# cblockyeeshok.net
KiCad netlist of a schematic drawn in EAGLE
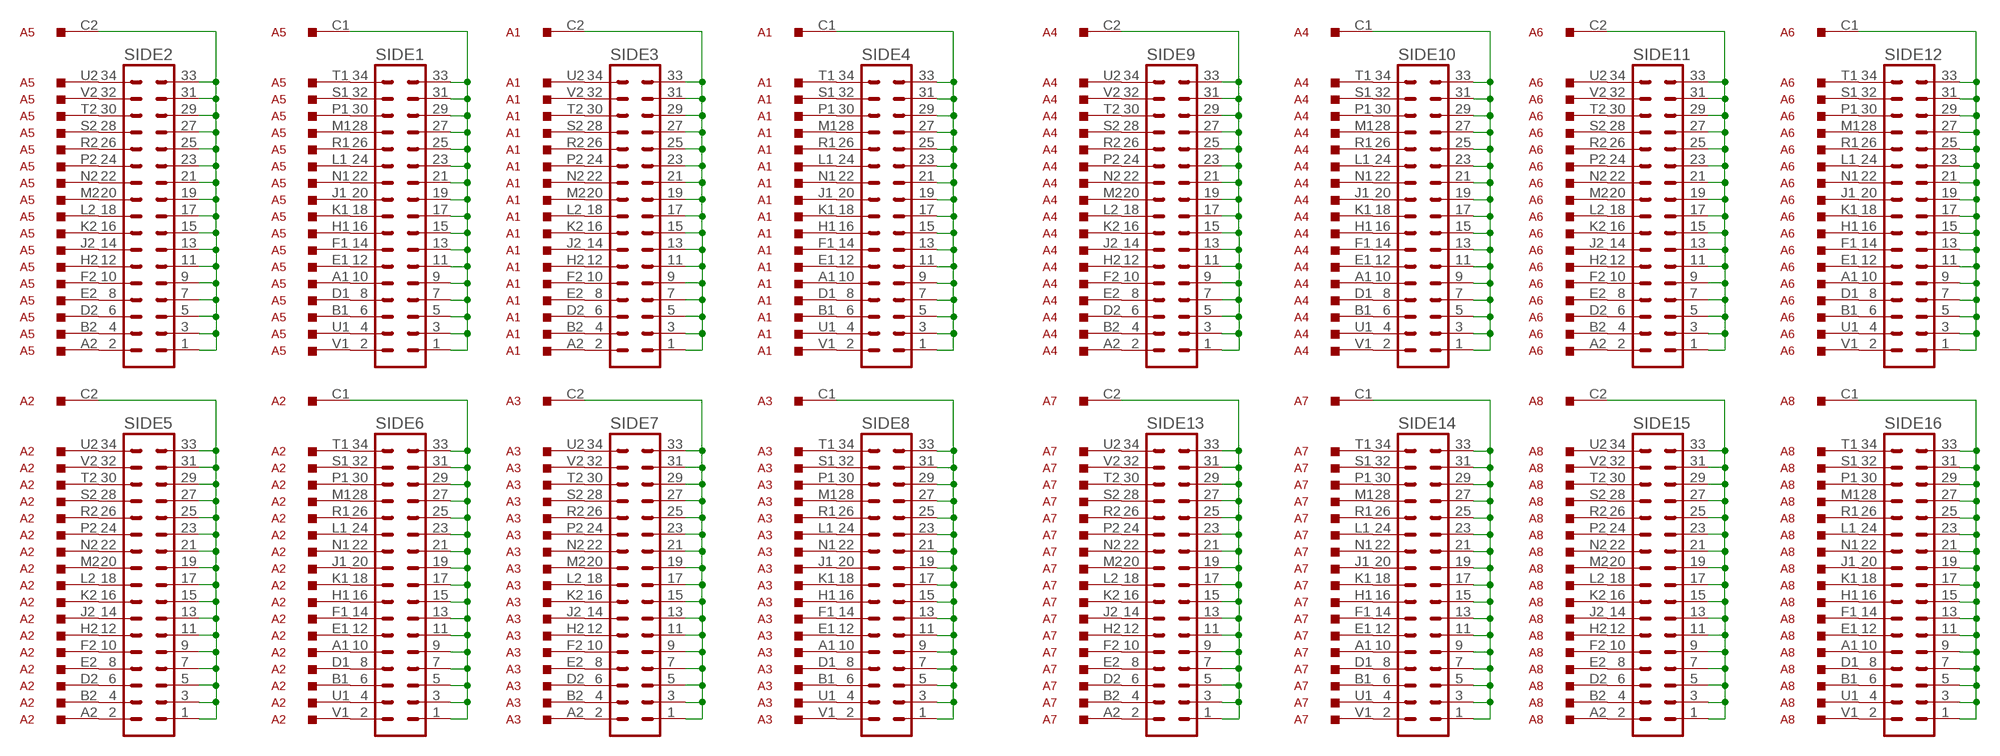
[diagram p0: schematic, sheet 1]

(export (version "E")
  (design (tool "Eeschema 10.0.6"))
  (components
    (comp (ref "A1")
      (value "M916")
      (footprint "eagle-import:H807")
      (libsource (lib "eagle-import") (part "M916"))
    )
    (comp (ref "A2")
      (value "M916")
      (footprint "eagle-import:H807")
      (libsource (lib "eagle-import") (part "M916"))
    )
    (comp (ref "A3")
      (value "M916")
      (footprint "eagle-import:H807")
      (libsource (lib "eagle-import") (part "M916"))
    )
    (comp (ref "A4")
      (value "M916")
      (footprint "eagle-import:H807")
      (libsource (lib "eagle-import") (part "M916"))
    )
    (comp (ref "A5")
      (value "M916")
      (footprint "eagle-import:H807")
      (libsource (lib "eagle-import") (part "M916"))
    )
    (comp (ref "A6")
      (value "M916")
      (footprint "eagle-import:H807")
      (libsource (lib "eagle-import") (part "M916"))
    )
    (comp (ref "A7")
      (value "M916")
      (footprint "eagle-import:H807")
      (libsource (lib "eagle-import") (part "M916"))
    )
    (comp (ref "A8")
      (value "M916")
      (footprint "eagle-import:H807")
      (libsource (lib "eagle-import") (part "M916"))
    )
    (comp (ref "SIDE1")
      (value "MA17-2")
      (footprint "eagle-import:MA17-2")
      (libsource (lib "eagle-import") (part "MA17-2"))
    )
    (comp (ref "SIDE2")
      (value "MA17-2")
      (footprint "eagle-import:MA17-2")
      (libsource (lib "eagle-import") (part "MA17-2"))
    )
    (comp (ref "SIDE3")
      (value "MA17-2")
      (footprint "eagle-import:MA17-2")
      (libsource (lib "eagle-import") (part "MA17-2"))
    )
    (comp (ref "SIDE4")
      (value "MA17-2")
      (footprint "eagle-import:MA17-2")
      (libsource (lib "eagle-import") (part "MA17-2"))
    )
    (comp (ref "SIDE5")
      (value "MA17-2")
      (footprint "eagle-import:MA17-2")
      (libsource (lib "eagle-import") (part "MA17-2"))
    )
    (comp (ref "SIDE6")
      (value "MA17-2")
      (footprint "eagle-import:MA17-2")
      (libsource (lib "eagle-import") (part "MA17-2"))
    )
    (comp (ref "SIDE7")
      (value "MA17-2")
      (footprint "eagle-import:MA17-2")
      (libsource (lib "eagle-import") (part "MA17-2"))
    )
    (comp (ref "SIDE8")
      (value "MA17-2")
      (footprint "eagle-import:MA17-2")
      (libsource (lib "eagle-import") (part "MA17-2"))
    )
    (comp (ref "SIDE9")
      (value "MA17-2")
      (footprint "eagle-import:MA17-2")
      (libsource (lib "eagle-import") (part "MA17-2"))
    )
    (comp (ref "SIDE10")
      (value "MA17-2")
      (footprint "eagle-import:MA17-2")
      (libsource (lib "eagle-import") (part "MA17-2"))
    )
    (comp (ref "SIDE11")
      (value "MA17-2")
      (footprint "eagle-import:MA17-2")
      (libsource (lib "eagle-import") (part "MA17-2"))
    )
    (comp (ref "SIDE12")
      (value "MA17-2")
      (footprint "eagle-import:MA17-2")
      (libsource (lib "eagle-import") (part "MA17-2"))
    )
    (comp (ref "SIDE13")
      (value "MA17-2")
      (footprint "eagle-import:MA17-2")
      (libsource (lib "eagle-import") (part "MA17-2"))
    )
    (comp (ref "SIDE14")
      (value "MA17-2")
      (footprint "eagle-import:MA17-2")
      (libsource (lib "eagle-import") (part "MA17-2"))
    )
    (comp (ref "SIDE15")
      (value "MA17-2")
      (footprint "eagle-import:MA17-2")
      (libsource (lib "eagle-import") (part "MA17-2"))
    )
    (comp (ref "SIDE16")
      (value "MA17-2")
      (footprint "eagle-import:MA17-2")
      (libsource (lib "eagle-import") (part "MA17-2"))
    )
  )
  (nets
    (net (code "1") (name "Net-(A1A-P$2)") (class "Default")
      (node (ref "A1") (pin "A1") (pinfunction "P$2_A1") (pintype "bidirectional"))
      (node (ref "SIDE4") (pin "10") (pinfunction "10_10") (pintype "passive"))
    )
    (net (code "2") (name "Net-(A1AA-P$2)") (class "Default")
      (node (ref "A1") (pin "R1") (pinfunction "P$2_R1") (pintype "bidirectional"))
      (node (ref "SIDE4") (pin "26") (pinfunction "26_26") (pintype "passive"))
    )
    (net (code "3") (name "Net-(A1AB-P$2)") (class "Default")
      (node (ref "A1") (pin "R2") (pinfunction "P$2_R2") (pintype "bidirectional"))
      (node (ref "SIDE3") (pin "26") (pinfunction "26_26") (pintype "passive"))
    )
    (net (code "4") (name "Net-(A1AC-P$2)") (class "Default")
      (node (ref "A1") (pin "S1") (pinfunction "P$2_S1") (pintype "bidirectional"))
      (node (ref "SIDE4") (pin "32") (pinfunction "32_32") (pintype "passive"))
    )
    (net (code "5") (name "Net-(A1AD-P$2)") (class "Default")
      (node (ref "A1") (pin "S2") (pinfunction "P$2_S2") (pintype "bidirectional"))
      (node (ref "SIDE3") (pin "28") (pinfunction "28_28") (pintype "passive"))
    )
    (net (code "6") (name "Net-(A1AE-P$2)") (class "Default")
      (node (ref "A1") (pin "T1") (pinfunction "P$2_T1") (pintype "bidirectional"))
      (node (ref "SIDE4") (pin "34") (pinfunction "34_34") (pintype "passive"))
    )
    (net (code "7") (name "Net-(A1AF-P$2)") (class "Default")
      (node (ref "A1") (pin "T2") (pinfunction "P$2_T2") (pintype "bidirectional"))
      (node (ref "SIDE3") (pin "30") (pinfunction "30_30") (pintype "passive"))
    )
    (net (code "8") (name "Net-(A1AG-P$2)") (class "Default")
      (node (ref "A1") (pin "U1") (pinfunction "P$2_U1") (pintype "bidirectional"))
      (node (ref "SIDE4") (pin "4") (pinfunction "4_4") (pintype "passive"))
    )
    (net (code "9") (name "Net-(A1AH-P$2)") (class "Default")
      (node (ref "A1") (pin "U2") (pinfunction "P$2_U2") (pintype "bidirectional"))
      (node (ref "SIDE3") (pin "34") (pinfunction "34_34") (pintype "passive"))
    )
    (net (code "10") (name "Net-(A1AI-P$2)") (class "Default")
      (node (ref "A1") (pin "V1") (pinfunction "P$2_V1") (pintype "bidirectional"))
      (node (ref "SIDE4") (pin "2") (pinfunction "2_2") (pintype "passive"))
    )
    (net (code "11") (name "Net-(A1AJ-P$2)") (class "Default")
      (node (ref "A1") (pin "V2") (pinfunction "P$2_V2") (pintype "bidirectional"))
      (node (ref "SIDE3") (pin "32") (pinfunction "32_32") (pintype "passive"))
    )
    (net (code "12") (name "Net-(A1B-P$2)") (class "Default")
      (node (ref "A1") (pin "A2") (pinfunction "P$2_A2") (pintype "bidirectional"))
      (node (ref "SIDE3") (pin "2") (pinfunction "2_2") (pintype "passive"))
    )
    (net (code "13") (name "Net-(A1C-P$2)") (class "Default")
      (node (ref "A1") (pin "B1") (pinfunction "P$2_B1") (pintype "bidirectional"))
      (node (ref "SIDE4") (pin "6") (pinfunction "6_6") (pintype "passive"))
    )
    (net (code "14") (name "Net-(A1D-P$2)") (class "Default")
      (node (ref "A1") (pin "B2") (pinfunction "P$2_B2") (pintype "bidirectional"))
      (node (ref "SIDE3") (pin "4") (pinfunction "4_4") (pintype "passive"))
    )
    (net (code "15") (name "Net-(A1E-P$2)") (class "Default")
      (node (ref "A1") (pin "C1") (pinfunction "P$2_C1") (pintype "bidirectional"))
      (node (ref "SIDE4") (pin "1") (pinfunction "1_1") (pintype "passive"))
      (node (ref "SIDE4") (pin "11") (pinfunction "11_11") (pintype "passive"))
      (node (ref "SIDE4") (pin "13") (pinfunction "13_13") (pintype "passive"))
      (node (ref "SIDE4") (pin "15") (pinfunction "15_15") (pintype "passive"))
      (node (ref "SIDE4") (pin "17") (pinfunction "17_17") (pintype "passive"))
      (node (ref "SIDE4") (pin "19") (pinfunction "19_19") (pintype "passive"))
      (node (ref "SIDE4") (pin "21") (pinfunction "21_21") (pintype "passive"))
      (node (ref "SIDE4") (pin "23") (pinfunction "23_23") (pintype "passive"))
      (node (ref "SIDE4") (pin "25") (pinfunction "25_25") (pintype "passive"))
      (node (ref "SIDE4") (pin "27") (pinfunction "27_27") (pintype "passive"))
      (node (ref "SIDE4") (pin "29") (pinfunction "29_29") (pintype "passive"))
      (node (ref "SIDE4") (pin "3") (pinfunction "3_3") (pintype "passive"))
      (node (ref "SIDE4") (pin "31") (pinfunction "31_31") (pintype "passive"))
      (node (ref "SIDE4") (pin "33") (pinfunction "33_33") (pintype "passive"))
      (node (ref "SIDE4") (pin "5") (pinfunction "5_5") (pintype "passive"))
      (node (ref "SIDE4") (pin "7") (pinfunction "7_7") (pintype "passive"))
      (node (ref "SIDE4") (pin "9") (pinfunction "9_9") (pintype "passive"))
    )
    (net (code "16") (name "Net-(A1F-P$2)") (class "Default")
      (node (ref "A1") (pin "C2") (pinfunction "P$2_C2") (pintype "bidirectional"))
      (node (ref "SIDE3") (pin "1") (pinfunction "1_1") (pintype "passive"))
      (node (ref "SIDE3") (pin "11") (pinfunction "11_11") (pintype "passive"))
      (node (ref "SIDE3") (pin "13") (pinfunction "13_13") (pintype "passive"))
      (node (ref "SIDE3") (pin "15") (pinfunction "15_15") (pintype "passive"))
      (node (ref "SIDE3") (pin "17") (pinfunction "17_17") (pintype "passive"))
      (node (ref "SIDE3") (pin "19") (pinfunction "19_19") (pintype "passive"))
      (node (ref "SIDE3") (pin "21") (pinfunction "21_21") (pintype "passive"))
      (node (ref "SIDE3") (pin "23") (pinfunction "23_23") (pintype "passive"))
      (node (ref "SIDE3") (pin "25") (pinfunction "25_25") (pintype "passive"))
      (node (ref "SIDE3") (pin "27") (pinfunction "27_27") (pintype "passive"))
      (node (ref "SIDE3") (pin "29") (pinfunction "29_29") (pintype "passive"))
      (node (ref "SIDE3") (pin "3") (pinfunction "3_3") (pintype "passive"))
      (node (ref "SIDE3") (pin "31") (pinfunction "31_31") (pintype "passive"))
      (node (ref "SIDE3") (pin "33") (pinfunction "33_33") (pintype "passive"))
      (node (ref "SIDE3") (pin "5") (pinfunction "5_5") (pintype "passive"))
      (node (ref "SIDE3") (pin "7") (pinfunction "7_7") (pintype "passive"))
      (node (ref "SIDE3") (pin "9") (pinfunction "9_9") (pintype "passive"))
    )
    (net (code "17") (name "Net-(A1G-P$2)") (class "Default")
      (node (ref "A1") (pin "D1") (pinfunction "P$2_D1") (pintype "bidirectional"))
      (node (ref "SIDE4") (pin "8") (pinfunction "8_8") (pintype "passive"))
    )
    (net (code "18") (name "Net-(A1H-P$2)") (class "Default")
      (node (ref "A1") (pin "D2") (pinfunction "P$2_D2") (pintype "bidirectional"))
      (node (ref "SIDE3") (pin "6") (pinfunction "6_6") (pintype "passive"))
    )
    (net (code "19") (name "Net-(A1I-P$2)") (class "Default")
      (node (ref "A1") (pin "E1") (pinfunction "P$2_E1") (pintype "bidirectional"))
      (node (ref "SIDE4") (pin "12") (pinfunction "12_12") (pintype "passive"))
    )
    (net (code "20") (name "Net-(A1J-P$2)") (class "Default")
      (node (ref "A1") (pin "E2") (pinfunction "P$2_E2") (pintype "bidirectional"))
      (node (ref "SIDE3") (pin "8") (pinfunction "8_8") (pintype "passive"))
    )
    (net (code "21") (name "Net-(A1K-P$2)") (class "Default")
      (node (ref "A1") (pin "F1") (pinfunction "P$2_F1") (pintype "bidirectional"))
      (node (ref "SIDE4") (pin "14") (pinfunction "14_14") (pintype "passive"))
    )
    (net (code "22") (name "Net-(A1L-P$2)") (class "Default")
      (node (ref "A1") (pin "F2") (pinfunction "P$2_F2") (pintype "bidirectional"))
      (node (ref "SIDE3") (pin "10") (pinfunction "10_10") (pintype "passive"))
    )
    (net (code "23") (name "Net-(A1M-P$2)") (class "Default")
      (node (ref "A1") (pin "H1") (pinfunction "P$2_H1") (pintype "bidirectional"))
      (node (ref "SIDE4") (pin "16") (pinfunction "16_16") (pintype "passive"))
    )
    (net (code "24") (name "Net-(A1N-P$2)") (class "Default")
      (node (ref "A1") (pin "H2") (pinfunction "P$2_H2") (pintype "bidirectional"))
      (node (ref "SIDE3") (pin "12") (pinfunction "12_12") (pintype "passive"))
    )
    (net (code "25") (name "Net-(A1O-P$2)") (class "Default")
      (node (ref "A1") (pin "J1") (pinfunction "P$2_J1") (pintype "bidirectional"))
      (node (ref "SIDE4") (pin "20") (pinfunction "20_20") (pintype "passive"))
    )
    (net (code "26") (name "Net-(A1P-P$2)") (class "Default")
      (node (ref "A1") (pin "J2") (pinfunction "P$2_J2") (pintype "bidirectional"))
      (node (ref "SIDE3") (pin "14") (pinfunction "14_14") (pintype "passive"))
    )
    (net (code "27") (name "Net-(A1Q-P$2)") (class "Default")
      (node (ref "A1") (pin "K1") (pinfunction "P$2_K1") (pintype "bidirectional"))
      (node (ref "SIDE4") (pin "18") (pinfunction "18_18") (pintype "passive"))
    )
    (net (code "28") (name "Net-(A1R-P$2)") (class "Default")
      (node (ref "A1") (pin "K2") (pinfunction "P$2_K2") (pintype "bidirectional"))
      (node (ref "SIDE3") (pin "16") (pinfunction "16_16") (pintype "passive"))
    )
    (net (code "29") (name "Net-(A1S-P$2)") (class "Default")
      (node (ref "A1") (pin "L1") (pinfunction "P$2_L1") (pintype "bidirectional"))
      (node (ref "SIDE4") (pin "24") (pinfunction "24_24") (pintype "passive"))
    )
    (net (code "30") (name "Net-(A1T-P$2)") (class "Default")
      (node (ref "A1") (pin "L2") (pinfunction "P$2_L2") (pintype "bidirectional"))
      (node (ref "SIDE3") (pin "18") (pinfunction "18_18") (pintype "passive"))
    )
    (net (code "31") (name "Net-(A1U-P$2)") (class "Default")
      (node (ref "A1") (pin "M1") (pinfunction "P$2_M1") (pintype "bidirectional"))
      (node (ref "SIDE4") (pin "28") (pinfunction "28_28") (pintype "passive"))
    )
    (net (code "32") (name "Net-(A1V-P$2)") (class "Default")
      (node (ref "A1") (pin "M2") (pinfunction "P$2_M2") (pintype "bidirectional"))
      (node (ref "SIDE3") (pin "20") (pinfunction "20_20") (pintype "passive"))
    )
    (net (code "33") (name "Net-(A1W-P$2)") (class "Default")
      (node (ref "A1") (pin "N1") (pinfunction "P$2_N1") (pintype "bidirectional"))
      (node (ref "SIDE4") (pin "22") (pinfunction "22_22") (pintype "passive"))
    )
    (net (code "34") (name "Net-(A1X-P$2)") (class "Default")
      (node (ref "A1") (pin "N2") (pinfunction "P$2_N2") (pintype "bidirectional"))
      (node (ref "SIDE3") (pin "22") (pinfunction "22_22") (pintype "passive"))
    )
    (net (code "35") (name "Net-(A1Y-P$2)") (class "Default")
      (node (ref "A1") (pin "P1") (pinfunction "P$2_P1") (pintype "bidirectional"))
      (node (ref "SIDE4") (pin "30") (pinfunction "30_30") (pintype "passive"))
    )
    (net (code "36") (name "Net-(A1Z-P$2)") (class "Default")
      (node (ref "A1") (pin "P2") (pinfunction "P$2_P2") (pintype "bidirectional"))
      (node (ref "SIDE3") (pin "24") (pinfunction "24_24") (pintype "passive"))
    )
    (net (code "37") (name "Net-(A2A-P$2)") (class "Default")
      (node (ref "A2") (pin "A1") (pinfunction "P$2_A1") (pintype "bidirectional"))
      (node (ref "SIDE6") (pin "10") (pinfunction "10_10") (pintype "passive"))
    )
    (net (code "38") (name "Net-(A2AA-P$2)") (class "Default")
      (node (ref "A2") (pin "R1") (pinfunction "P$2_R1") (pintype "bidirectional"))
      (node (ref "SIDE6") (pin "26") (pinfunction "26_26") (pintype "passive"))
    )
    (net (code "39") (name "Net-(A2AB-P$2)") (class "Default")
      (node (ref "A2") (pin "R2") (pinfunction "P$2_R2") (pintype "bidirectional"))
      (node (ref "SIDE5") (pin "26") (pinfunction "26_26") (pintype "passive"))
    )
    (net (code "40") (name "Net-(A2AC-P$2)") (class "Default")
      (node (ref "A2") (pin "S1") (pinfunction "P$2_S1") (pintype "bidirectional"))
      (node (ref "SIDE6") (pin "32") (pinfunction "32_32") (pintype "passive"))
    )
    (net (code "41") (name "Net-(A2AD-P$2)") (class "Default")
      (node (ref "A2") (pin "S2") (pinfunction "P$2_S2") (pintype "bidirectional"))
      (node (ref "SIDE5") (pin "28") (pinfunction "28_28") (pintype "passive"))
    )
    (net (code "42") (name "Net-(A2AE-P$2)") (class "Default")
      (node (ref "A2") (pin "T1") (pinfunction "P$2_T1") (pintype "bidirectional"))
      (node (ref "SIDE6") (pin "34") (pinfunction "34_34") (pintype "passive"))
    )
    (net (code "43") (name "Net-(A2AF-P$2)") (class "Default")
      (node (ref "A2") (pin "T2") (pinfunction "P$2_T2") (pintype "bidirectional"))
      (node (ref "SIDE5") (pin "30") (pinfunction "30_30") (pintype "passive"))
    )
    (net (code "44") (name "Net-(A2AG-P$2)") (class "Default")
      (node (ref "A2") (pin "U1") (pinfunction "P$2_U1") (pintype "bidirectional"))
      (node (ref "SIDE6") (pin "4") (pinfunction "4_4") (pintype "passive"))
    )
    (net (code "45") (name "Net-(A2AH-P$2)") (class "Default")
      (node (ref "A2") (pin "U2") (pinfunction "P$2_U2") (pintype "bidirectional"))
      (node (ref "SIDE5") (pin "34") (pinfunction "34_34") (pintype "passive"))
    )
    (net (code "46") (name "Net-(A2AI-P$2)") (class "Default")
      (node (ref "A2") (pin "V1") (pinfunction "P$2_V1") (pintype "bidirectional"))
      (node (ref "SIDE6") (pin "2") (pinfunction "2_2") (pintype "passive"))
    )
    (net (code "47") (name "Net-(A2AJ-P$2)") (class "Default")
      (node (ref "A2") (pin "V2") (pinfunction "P$2_V2") (pintype "bidirectional"))
      (node (ref "SIDE5") (pin "32") (pinfunction "32_32") (pintype "passive"))
    )
    (net (code "48") (name "Net-(A2B-P$2)") (class "Default")
      (node (ref "A2") (pin "A2") (pinfunction "P$2_A2") (pintype "bidirectional"))
      (node (ref "SIDE5") (pin "2") (pinfunction "2_2") (pintype "passive"))
    )
    (net (code "49") (name "Net-(A2C-P$2)") (class "Default")
      (node (ref "A2") (pin "B1") (pinfunction "P$2_B1") (pintype "bidirectional"))
      (node (ref "SIDE6") (pin "6") (pinfunction "6_6") (pintype "passive"))
    )
    (net (code "50") (name "Net-(A2D-P$2)") (class "Default")
      (node (ref "A2") (pin "B2") (pinfunction "P$2_B2") (pintype "bidirectional"))
      (node (ref "SIDE5") (pin "4") (pinfunction "4_4") (pintype "passive"))
    )
    (net (code "51") (name "Net-(A2E-P$2)") (class "Default")
      (node (ref "A2") (pin "C1") (pinfunction "P$2_C1") (pintype "bidirectional"))
      (node (ref "SIDE6") (pin "1") (pinfunction "1_1") (pintype "passive"))
      (node (ref "SIDE6") (pin "11") (pinfunction "11_11") (pintype "passive"))
      (node (ref "SIDE6") (pin "13") (pinfunction "13_13") (pintype "passive"))
      (node (ref "SIDE6") (pin "15") (pinfunction "15_15") (pintype "passive"))
      (node (ref "SIDE6") (pin "17") (pinfunction "17_17") (pintype "passive"))
      (node (ref "SIDE6") (pin "19") (pinfunction "19_19") (pintype "passive"))
      (node (ref "SIDE6") (pin "21") (pinfunction "21_21") (pintype "passive"))
      (node (ref "SIDE6") (pin "23") (pinfunction "23_23") (pintype "passive"))
      (node (ref "SIDE6") (pin "25") (pinfunction "25_25") (pintype "passive"))
      (node (ref "SIDE6") (pin "27") (pinfunction "27_27") (pintype "passive"))
      (node (ref "SIDE6") (pin "29") (pinfunction "29_29") (pintype "passive"))
      (node (ref "SIDE6") (pin "3") (pinfunction "3_3") (pintype "passive"))
      (node (ref "SIDE6") (pin "31") (pinfunction "31_31") (pintype "passive"))
      (node (ref "SIDE6") (pin "33") (pinfunction "33_33") (pintype "passive"))
      (node (ref "SIDE6") (pin "5") (pinfunction "5_5") (pintype "passive"))
      (node (ref "SIDE6") (pin "7") (pinfunction "7_7") (pintype "passive"))
      (node (ref "SIDE6") (pin "9") (pinfunction "9_9") (pintype "passive"))
    )
    (net (code "52") (name "Net-(A2F-P$2)") (class "Default")
      (node (ref "A2") (pin "C2") (pinfunction "P$2_C2") (pintype "bidirectional"))
      (node (ref "SIDE5") (pin "1") (pinfunction "1_1") (pintype "passive"))
      (node (ref "SIDE5") (pin "11") (pinfunction "11_11") (pintype "passive"))
      (node (ref "SIDE5") (pin "13") (pinfunction "13_13") (pintype "passive"))
      (node (ref "SIDE5") (pin "15") (pinfunction "15_15") (pintype "passive"))
      (node (ref "SIDE5") (pin "17") (pinfunction "17_17") (pintype "passive"))
      (node (ref "SIDE5") (pin "19") (pinfunction "19_19") (pintype "passive"))
      (node (ref "SIDE5") (pin "21") (pinfunction "21_21") (pintype "passive"))
      (node (ref "SIDE5") (pin "23") (pinfunction "23_23") (pintype "passive"))
      (node (ref "SIDE5") (pin "25") (pinfunction "25_25") (pintype "passive"))
      (node (ref "SIDE5") (pin "27") (pinfunction "27_27") (pintype "passive"))
      (node (ref "SIDE5") (pin "29") (pinfunction "29_29") (pintype "passive"))
      (node (ref "SIDE5") (pin "3") (pinfunction "3_3") (pintype "passive"))
      (node (ref "SIDE5") (pin "31") (pinfunction "31_31") (pintype "passive"))
      (node (ref "SIDE5") (pin "33") (pinfunction "33_33") (pintype "passive"))
      (node (ref "SIDE5") (pin "5") (pinfunction "5_5") (pintype "passive"))
      (node (ref "SIDE5") (pin "7") (pinfunction "7_7") (pintype "passive"))
      (node (ref "SIDE5") (pin "9") (pinfunction "9_9") (pintype "passive"))
    )
    (net (code "53") (name "Net-(A2G-P$2)") (class "Default")
      (node (ref "A2") (pin "D1") (pinfunction "P$2_D1") (pintype "bidirectional"))
      (node (ref "SIDE6") (pin "8") (pinfunction "8_8") (pintype "passive"))
    )
    (net (code "54") (name "Net-(A2H-P$2)") (class "Default")
      (node (ref "A2") (pin "D2") (pinfunction "P$2_D2") (pintype "bidirectional"))
      (node (ref "SIDE5") (pin "6") (pinfunction "6_6") (pintype "passive"))
    )
    (net (code "55") (name "Net-(A2I-P$2)") (class "Default")
      (node (ref "A2") (pin "E1") (pinfunction "P$2_E1") (pintype "bidirectional"))
      (node (ref "SIDE6") (pin "12") (pinfunction "12_12") (pintype "passive"))
    )
    (net (code "56") (name "Net-(A2J-P$2)") (class "Default")
      (node (ref "A2") (pin "E2") (pinfunction "P$2_E2") (pintype "bidirectional"))
      (node (ref "SIDE5") (pin "8") (pinfunction "8_8") (pintype "passive"))
    )
    (net (code "57") (name "Net-(A2K-P$2)") (class "Default")
      (node (ref "A2") (pin "F1") (pinfunction "P$2_F1") (pintype "bidirectional"))
      (node (ref "SIDE6") (pin "14") (pinfunction "14_14") (pintype "passive"))
    )
    (net (code "58") (name "Net-(A2L-P$2)") (class "Default")
      (node (ref "A2") (pin "F2") (pinfunction "P$2_F2") (pintype "bidirectional"))
      (node (ref "SIDE5") (pin "10") (pinfunction "10_10") (pintype "passive"))
    )
    (net (code "59") (name "Net-(A2M-P$2)") (class "Default")
      (node (ref "A2") (pin "H1") (pinfunction "P$2_H1") (pintype "bidirectional"))
      (node (ref "SIDE6") (pin "16") (pinfunction "16_16") (pintype "passive"))
    )
    (net (code "60") (name "Net-(A2N-P$2)") (class "Default")
      (node (ref "A2") (pin "H2") (pinfunction "P$2_H2") (pintype "bidirectional"))
      (node (ref "SIDE5") (pin "12") (pinfunction "12_12") (pintype "passive"))
    )
    (net (code "61") (name "Net-(A2O-P$2)") (class "Default")
      (node (ref "A2") (pin "J1") (pinfunction "P$2_J1") (pintype "bidirectional"))
      (node (ref "SIDE6") (pin "20") (pinfunction "20_20") (pintype "passive"))
    )
    (net (code "62") (name "Net-(A2P-P$2)") (class "Default")
      (node (ref "A2") (pin "J2") (pinfunction "P$2_J2") (pintype "bidirectional"))
      (node (ref "SIDE5") (pin "14") (pinfunction "14_14") (pintype "passive"))
    )
    (net (code "63") (name "Net-(A2Q-P$2)") (class "Default")
      (node (ref "A2") (pin "K1") (pinfunction "P$2_K1") (pintype "bidirectional"))
      (node (ref "SIDE6") (pin "18") (pinfunction "18_18") (pintype "passive"))
    )
    (net (code "64") (name "Net-(A2R-P$2)") (class "Default")
      (node (ref "A2") (pin "K2") (pinfunction "P$2_K2") (pintype "bidirectional"))
      (node (ref "SIDE5") (pin "16") (pinfunction "16_16") (pintype "passive"))
    )
    (net (code "65") (name "Net-(A2S-P$2)") (class "Default")
      (node (ref "A2") (pin "L1") (pinfunction "P$2_L1") (pintype "bidirectional"))
      (node (ref "SIDE6") (pin "24") (pinfunction "24_24") (pintype "passive"))
    )
    (net (code "66") (name "Net-(A2T-P$2)") (class "Default")
      (node (ref "A2") (pin "L2") (pinfunction "P$2_L2") (pintype "bidirectional"))
      (node (ref "SIDE5") (pin "18") (pinfunction "18_18") (pintype "passive"))
    )
    (net (code "67") (name "Net-(A2U-P$2)") (class "Default")
      (node (ref "A2") (pin "M1") (pinfunction "P$2_M1") (pintype "bidirectional"))
      (node (ref "SIDE6") (pin "28") (pinfunction "28_28") (pintype "passive"))
    )
    (net (code "68") (name "Net-(A2V-P$2)") (class "Default")
      (node (ref "A2") (pin "M2") (pinfunction "P$2_M2") (pintype "bidirectional"))
      (node (ref "SIDE5") (pin "20") (pinfunction "20_20") (pintype "passive"))
    )
    (net (code "69") (name "Net-(A2W-P$2)") (class "Default")
      (node (ref "A2") (pin "N1") (pinfunction "P$2_N1") (pintype "bidirectional"))
      (node (ref "SIDE6") (pin "22") (pinfunction "22_22") (pintype "passive"))
    )
    (net (code "70") (name "Net-(A2X-P$2)") (class "Default")
      (node (ref "A2") (pin "N2") (pinfunction "P$2_N2") (pintype "bidirectional"))
      (node (ref "SIDE5") (pin "22") (pinfunction "22_22") (pintype "passive"))
    )
    (net (code "71") (name "Net-(A2Y-P$2)") (class "Default")
      (node (ref "A2") (pin "P1") (pinfunction "P$2_P1") (pintype "bidirectional"))
      (node (ref "SIDE6") (pin "30") (pinfunction "30_30") (pintype "passive"))
    )
    (net (code "72") (name "Net-(A2Z-P$2)") (class "Default")
      (node (ref "A2") (pin "P2") (pinfunction "P$2_P2") (pintype "bidirectional"))
      (node (ref "SIDE5") (pin "24") (pinfunction "24_24") (pintype "passive"))
    )
    (net (code "73") (name "Net-(A3A-P$2)") (class "Default")
      (node (ref "A3") (pin "A1") (pinfunction "P$2_A1") (pintype "bidirectional"))
      (node (ref "SIDE8") (pin "10") (pinfunction "10_10") (pintype "passive"))
    )
    (net (code "74") (name "Net-(A3AA-P$2)") (class "Default")
      (node (ref "A3") (pin "R1") (pinfunction "P$2_R1") (pintype "bidirectional"))
      (node (ref "SIDE8") (pin "26") (pinfunction "26_26") (pintype "passive"))
    )
    (net (code "75") (name "Net-(A3AB-P$2)") (class "Default")
      (node (ref "A3") (pin "R2") (pinfunction "P$2_R2") (pintype "bidirectional"))
      (node (ref "SIDE7") (pin "26") (pinfunction "26_26") (pintype "passive"))
    )
    (net (code "76") (name "Net-(A3AC-P$2)") (class "Default")
      (node (ref "A3") (pin "S1") (pinfunction "P$2_S1") (pintype "bidirectional"))
      (node (ref "SIDE8") (pin "32") (pinfunction "32_32") (pintype "passive"))
    )
    (net (code "77") (name "Net-(A3AD-P$2)") (class "Default")
      (node (ref "A3") (pin "S2") (pinfunction "P$2_S2") (pintype "bidirectional"))
      (node (ref "SIDE7") (pin "28") (pinfunction "28_28") (pintype "passive"))
    )
    (net (code "78") (name "Net-(A3AE-P$2)") (class "Default")
      (node (ref "A3") (pin "T1") (pinfunction "P$2_T1") (pintype "bidirectional"))
      (node (ref "SIDE8") (pin "34") (pinfunction "34_34") (pintype "passive"))
    )
    (net (code "79") (name "Net-(A3AF-P$2)") (class "Default")
      (node (ref "A3") (pin "T2") (pinfunction "P$2_T2") (pintype "bidirectional"))
      (node (ref "SIDE7") (pin "30") (pinfunction "30_30") (pintype "passive"))
    )
    (net (code "80") (name "Net-(A3AG-P$2)") (class "Default")
      (node (ref "A3") (pin "U1") (pinfunction "P$2_U1") (pintype "bidirectional"))
      (node (ref "SIDE8") (pin "4") (pinfunction "4_4") (pintype "passive"))
    )
    (net (code "81") (name "Net-(A3AH-P$2)") (class "Default")
      (node (ref "A3") (pin "U2") (pinfunction "P$2_U2") (pintype "bidirectional"))
      (node (ref "SIDE7") (pin "34") (pinfunction "34_34") (pintype "passive"))
    )
    (net (code "82") (name "Net-(A3AI-P$2)") (class "Default")
      (node (ref "A3") (pin "V1") (pinfunction "P$2_V1") (pintype "bidirectional"))
      (node (ref "SIDE8") (pin "2") (pinfunction "2_2") (pintype "passive"))
    )
    (net (code "83") (name "Net-(A3AJ-P$2)") (class "Default")
      (node (ref "A3") (pin "V2") (pinfunction "P$2_V2") (pintype "bidirectional"))
      (node (ref "SIDE7") (pin "32") (pinfunction "32_32") (pintype "passive"))
    )
    (net (code "84") (name "Net-(A3B-P$2)") (class "Default")
      (node (ref "A3") (pin "A2") (pinfunction "P$2_A2") (pintype "bidirectional"))
      (node (ref "SIDE7") (pin "2") (pinfunction "2_2") (pintype "passive"))
    )
    (net (code "85") (name "Net-(A3C-P$2)") (class "Default")
      (node (ref "A3") (pin "B1") (pinfunction "P$2_B1") (pintype "bidirectional"))
      (node (ref "SIDE8") (pin "6") (pinfunction "6_6") (pintype "passive"))
    )
    (net (code "86") (name "Net-(A3D-P$2)") (class "Default")
      (node (ref "A3") (pin "B2") (pinfunction "P$2_B2") (pintype "bidirectional"))
      (node (ref "SIDE7") (pin "4") (pinfunction "4_4") (pintype "passive"))
    )
    (net (code "87") (name "Net-(A3E-P$2)") (class "Default")
      (node (ref "A3") (pin "C1") (pinfunction "P$2_C1") (pintype "bidirectional"))
      (node (ref "SIDE8") (pin "1") (pinfunction "1_1") (pintype "passive"))
      (node (ref "SIDE8") (pin "11") (pinfunction "11_11") (pintype "passive"))
      (node (ref "SIDE8") (pin "13") (pinfunction "13_13") (pintype "passive"))
      (node (ref "SIDE8") (pin "15") (pinfunction "15_15") (pintype "passive"))
      (node (ref "SIDE8") (pin "17") (pinfunction "17_17") (pintype "passive"))
      (node (ref "SIDE8") (pin "19") (pinfunction "19_19") (pintype "passive"))
      (node (ref "SIDE8") (pin "21") (pinfunction "21_21") (pintype "passive"))
      (node (ref "SIDE8") (pin "23") (pinfunction "23_23") (pintype "passive"))
      (node (ref "SIDE8") (pin "25") (pinfunction "25_25") (pintype "passive"))
      (node (ref "SIDE8") (pin "27") (pinfunction "27_27") (pintype "passive"))
      (node (ref "SIDE8") (pin "29") (pinfunction "29_29") (pintype "passive"))
      (node (ref "SIDE8") (pin "3") (pinfunction "3_3") (pintype "passive"))
      (node (ref "SIDE8") (pin "31") (pinfunction "31_31") (pintype "passive"))
      (node (ref "SIDE8") (pin "33") (pinfunction "33_33") (pintype "passive"))
      (node (ref "SIDE8") (pin "5") (pinfunction "5_5") (pintype "passive"))
      (node (ref "SIDE8") (pin "7") (pinfunction "7_7") (pintype "passive"))
      (node (ref "SIDE8") (pin "9") (pinfunction "9_9") (pintype "passive"))
    )
    (net (code "88") (name "Net-(A3F-P$2)") (class "Default")
      (node (ref "A3") (pin "C2") (pinfunction "P$2_C2") (pintype "bidirectional"))
      (node (ref "SIDE7") (pin "1") (pinfunction "1_1") (pintype "passive"))
      (node (ref "SIDE7") (pin "11") (pinfunction "11_11") (pintype "passive"))
      (node (ref "SIDE7") (pin "13") (pinfunction "13_13") (pintype "passive"))
      (node (ref "SIDE7") (pin "15") (pinfunction "15_15") (pintype "passive"))
      (node (ref "SIDE7") (pin "17") (pinfunction "17_17") (pintype "passive"))
      (node (ref "SIDE7") (pin "19") (pinfunction "19_19") (pintype "passive"))
      (node (ref "SIDE7") (pin "21") (pinfunction "21_21") (pintype "passive"))
      (node (ref "SIDE7") (pin "23") (pinfunction "23_23") (pintype "passive"))
      (node (ref "SIDE7") (pin "25") (pinfunction "25_25") (pintype "passive"))
      (node (ref "SIDE7") (pin "27") (pinfunction "27_27") (pintype "passive"))
      (node (ref "SIDE7") (pin "29") (pinfunction "29_29") (pintype "passive"))
      (node (ref "SIDE7") (pin "3") (pinfunction "3_3") (pintype "passive"))
      (node (ref "SIDE7") (pin "31") (pinfunction "31_31") (pintype "passive"))
      (node (ref "SIDE7") (pin "33") (pinfunction "33_33") (pintype "passive"))
      (node (ref "SIDE7") (pin "5") (pinfunction "5_5") (pintype "passive"))
      (node (ref "SIDE7") (pin "7") (pinfunction "7_7") (pintype "passive"))
      (node (ref "SIDE7") (pin "9") (pinfunction "9_9") (pintype "passive"))
    )
    (net (code "89") (name "Net-(A3G-P$2)") (class "Default")
      (node (ref "A3") (pin "D1") (pinfunction "P$2_D1") (pintype "bidirectional"))
      (node (ref "SIDE8") (pin "8") (pinfunction "8_8") (pintype "passive"))
    )
    (net (code "90") (name "Net-(A3H-P$2)") (class "Default")
      (node (ref "A3") (pin "D2") (pinfunction "P$2_D2") (pintype "bidirectional"))
      (node (ref "SIDE7") (pin "6") (pinfunction "6_6") (pintype "passive"))
    )
    (net (code "91") (name "Net-(A3I-P$2)") (class "Default")
      (node (ref "A3") (pin "E1") (pinfunction "P$2_E1") (pintype "bidirectional"))
      (node (ref "SIDE8") (pin "12") (pinfunction "12_12") (pintype "passive"))
    )
    (net (code "92") (name "Net-(A3J-P$2)") (class "Default")
      (node (ref "A3") (pin "E2") (pinfunction "P$2_E2") (pintype "bidirectional"))
      (node (ref "SIDE7") (pin "8") (pinfunction "8_8") (pintype "passive"))
    )
    (net (code "93") (name "Net-(A3K-P$2)") (class "Default")
      (node (ref "A3") (pin "F1") (pinfunction "P$2_F1") (pintype "bidirectional"))
      (node (ref "SIDE8") (pin "14") (pinfunction "14_14") (pintype "passive"))
    )
    (net (code "94") (name "Net-(A3L-P$2)") (class "Default")
      (node (ref "A3") (pin "F2") (pinfunction "P$2_F2") (pintype "bidirectional"))
      (node (ref "SIDE7") (pin "10") (pinfunction "10_10") (pintype "passive"))
    )
    (net (code "95") (name "Net-(A3M-P$2)") (class "Default")
      (node (ref "A3") (pin "H1") (pinfunction "P$2_H1") (pintype "bidirectional"))
      (node (ref "SIDE8") (pin "16") (pinfunction "16_16") (pintype "passive"))
    )
    (net (code "96") (name "Net-(A3N-P$2)") (class "Default")
      (node (ref "A3") (pin "H2") (pinfunction "P$2_H2") (pintype "bidirectional"))
      (node (ref "SIDE7") (pin "12") (pinfunction "12_12") (pintype "passive"))
    )
    (net (code "97") (name "Net-(A3O-P$2)") (class "Default")
      (node (ref "A3") (pin "J1") (pinfunction "P$2_J1") (pintype "bidirectional"))
      (node (ref "SIDE8") (pin "20") (pinfunction "20_20") (pintype "passive"))
    )
    (net (code "98") (name "Net-(A3P-P$2)") (class "Default")
      (node (ref "A3") (pin "J2") (pinfunction "P$2_J2") (pintype "bidirectional"))
      (node (ref "SIDE7") (pin "14") (pinfunction "14_14") (pintype "passive"))
    )
    (net (code "99") (name "Net-(A3Q-P$2)") (class "Default")
      (node (ref "A3") (pin "K1") (pinfunction "P$2_K1") (pintype "bidirectional"))
      (node (ref "SIDE8") (pin "18") (pinfunction "18_18") (pintype "passive"))
    )
    (net (code "100") (name "Net-(A3R-P$2)") (class "Default")
      (node (ref "A3") (pin "K2") (pinfunction "P$2_K2") (pintype "bidirectional"))
      (node (ref "SIDE7") (pin "16") (pinfunction "16_16") (pintype "passive"))
    )
    (net (code "101") (name "Net-(A3S-P$2)") (class "Default")
      (node (ref "A3") (pin "L1") (pinfunction "P$2_L1") (pintype "bidirectional"))
      (node (ref "SIDE8") (pin "24") (pinfunction "24_24") (pintype "passive"))
    )
    (net (code "102") (name "Net-(A3T-P$2)") (class "Default")
      (node (ref "A3") (pin "L2") (pinfunction "P$2_L2") (pintype "bidirectional"))
      (node (ref "SIDE7") (pin "18") (pinfunction "18_18") (pintype "passive"))
    )
    (net (code "103") (name "Net-(A3U-P$2)") (class "Default")
      (node (ref "A3") (pin "M1") (pinfunction "P$2_M1") (pintype "bidirectional"))
      (node (ref "SIDE8") (pin "28") (pinfunction "28_28") (pintype "passive"))
    )
    (net (code "104") (name "Net-(A3V-P$2)") (class "Default")
      (node (ref "A3") (pin "M2") (pinfunction "P$2_M2") (pintype "bidirectional"))
      (node (ref "SIDE7") (pin "20") (pinfunction "20_20") (pintype "passive"))
    )
    (net (code "105") (name "Net-(A3W-P$2)") (class "Default")
      (node (ref "A3") (pin "N1") (pinfunction "P$2_N1") (pintype "bidirectional"))
      (node (ref "SIDE8") (pin "22") (pinfunction "22_22") (pintype "passive"))
    )
    (net (code "106") (name "Net-(A3X-P$2)") (class "Default")
      (node (ref "A3") (pin "N2") (pinfunction "P$2_N2") (pintype "bidirectional"))
      (node (ref "SIDE7") (pin "22") (pinfunction "22_22") (pintype "passive"))
    )
    (net (code "107") (name "Net-(A3Y-P$2)") (class "Default")
      (node (ref "A3") (pin "P1") (pinfunction "P$2_P1") (pintype "bidirectional"))
      (node (ref "SIDE8") (pin "30") (pinfunction "30_30") (pintype "passive"))
    )
    (net (code "108") (name "Net-(A3Z-P$2)") (class "Default")
      (node (ref "A3") (pin "P2") (pinfunction "P$2_P2") (pintype "bidirectional"))
      (node (ref "SIDE7") (pin "24") (pinfunction "24_24") (pintype "passive"))
    )
    (net (code "109") (name "Net-(A4A-P$2)") (class "Default")
      (node (ref "A4") (pin "A1") (pinfunction "P$2_A1") (pintype "bidirectional"))
      (node (ref "SIDE10") (pin "10") (pinfunction "10_10") (pintype "passive"))
    )
    (net (code "110") (name "Net-(A4AA-P$2)") (class "Default")
      (node (ref "A4") (pin "R1") (pinfunction "P$2_R1") (pintype "bidirectional"))
      (node (ref "SIDE10") (pin "26") (pinfunction "26_26") (pintype "passive"))
    )
    (net (code "111") (name "Net-(A4AB-P$2)") (class "Default")
      (node (ref "A4") (pin "R2") (pinfunction "P$2_R2") (pintype "bidirectional"))
      (node (ref "SIDE9") (pin "26") (pinfunction "26_26") (pintype "passive"))
    )
    (net (code "112") (name "Net-(A4AC-P$2)") (class "Default")
      (node (ref "A4") (pin "S1") (pinfunction "P$2_S1") (pintype "bidirectional"))
      (node (ref "SIDE10") (pin "32") (pinfunction "32_32") (pintype "passive"))
    )
    (net (code "113") (name "Net-(A4AD-P$2)") (class "Default")
      (node (ref "A4") (pin "S2") (pinfunction "P$2_S2") (pintype "bidirectional"))
      (node (ref "SIDE9") (pin "28") (pinfunction "28_28") (pintype "passive"))
    )
    (net (code "114") (name "Net-(A4AE-P$2)") (class "Default")
      (node (ref "A4") (pin "T1") (pinfunction "P$2_T1") (pintype "bidirectional"))
      (node (ref "SIDE10") (pin "34") (pinfunction "34_34") (pintype "passive"))
    )
    (net (code "115") (name "Net-(A4AF-P$2)") (class "Default")
      (node (ref "A4") (pin "T2") (pinfunction "P$2_T2") (pintype "bidirectional"))
      (node (ref "SIDE9") (pin "30") (pinfunction "30_30") (pintype "passive"))
    )
    (net (code "116") (name "Net-(A4AG-P$2)") (class "Default")
      (node (ref "A4") (pin "U1") (pinfunction "P$2_U1") (pintype "bidirectional"))
      (node (ref "SIDE10") (pin "4") (pinfunction "4_4") (pintype "passive"))
    )
    (net (code "117") (name "Net-(A4AH-P$2)") (class "Default")
      (node (ref "A4") (pin "U2") (pinfunction "P$2_U2") (pintype "bidirectional"))
      (node (ref "SIDE9") (pin "34") (pinfunction "34_34") (pintype "passive"))
    )
    (net (code "118") (name "Net-(A4AI-P$2)") (class "Default")
      (node (ref "A4") (pin "V1") (pinfunction "P$2_V1") (pintype "bidirectional"))
      (node (ref "SIDE10") (pin "2") (pinfunction "2_2") (pintype "passive"))
    )
    (net (code "119") (name "Net-(A4AJ-P$2)") (class "Default")
      (node (ref "A4") (pin "V2") (pinfunction "P$2_V2") (pintype "bidirectional"))
      (node (ref "SIDE9") (pin "32") (pinfunction "32_32") (pintype "passive"))
    )
    (net (code "120") (name "Net-(A4B-P$2)") (class "Default")
      (node (ref "A4") (pin "A2") (pinfunction "P$2_A2") (pintype "bidirectional"))
      (node (ref "SIDE9") (pin "2") (pinfunction "2_2") (pintype "passive"))
    )
    (net (code "121") (name "Net-(A4C-P$2)") (class "Default")
      (node (ref "A4") (pin "B1") (pinfunction "P$2_B1") (pintype "bidirectional"))
      (node (ref "SIDE10") (pin "6") (pinfunction "6_6") (pintype "passive"))
    )
    (net (code "122") (name "Net-(A4D-P$2)") (class "Default")
      (node (ref "A4") (pin "B2") (pinfunction "P$2_B2") (pintype "bidirectional"))
      (node (ref "SIDE9") (pin "4") (pinfunction "4_4") (pintype "passive"))
    )
    (net (code "123") (name "Net-(A4E-P$2)") (class "Default")
      (node (ref "A4") (pin "C1") (pinfunction "P$2_C1") (pintype "bidirectional"))
      (node (ref "SIDE10") (pin "1") (pinfunction "1_1") (pintype "passive"))
      (node (ref "SIDE10") (pin "11") (pinfunction "11_11") (pintype "passive"))
      (node (ref "SIDE10") (pin "13") (pinfunction "13_13") (pintype "passive"))
      (node (ref "SIDE10") (pin "15") (pinfunction "15_15") (pintype "passive"))
      (node (ref "SIDE10") (pin "17") (pinfunction "17_17") (pintype "passive"))
      (node (ref "SIDE10") (pin "19") (pinfunction "19_19") (pintype "passive"))
      (node (ref "SIDE10") (pin "21") (pinfunction "21_21") (pintype "passive"))
      (node (ref "SIDE10") (pin "23") (pinfunction "23_23") (pintype "passive"))
      (node (ref "SIDE10") (pin "25") (pinfunction "25_25") (pintype "passive"))
      (node (ref "SIDE10") (pin "27") (pinfunction "27_27") (pintype "passive"))
      (node (ref "SIDE10") (pin "29") (pinfunction "29_29") (pintype "passive"))
      (node (ref "SIDE10") (pin "3") (pinfunction "3_3") (pintype "passive"))
      (node (ref "SIDE10") (pin "31") (pinfunction "31_31") (pintype "passive"))
      (node (ref "SIDE10") (pin "33") (pinfunction "33_33") (pintype "passive"))
      (node (ref "SIDE10") (pin "5") (pinfunction "5_5") (pintype "passive"))
      (node (ref "SIDE10") (pin "7") (pinfunction "7_7") (pintype "passive"))
      (node (ref "SIDE10") (pin "9") (pinfunction "9_9") (pintype "passive"))
    )
    (net (code "124") (name "Net-(A4F-P$2)") (class "Default")
      (node (ref "A4") (pin "C2") (pinfunction "P$2_C2") (pintype "bidirectional"))
      (node (ref "SIDE9") (pin "1") (pinfunction "1_1") (pintype "passive"))
      (node (ref "SIDE9") (pin "11") (pinfunction "11_11") (pintype "passive"))
      (node (ref "SIDE9") (pin "13") (pinfunction "13_13") (pintype "passive"))
      (node (ref "SIDE9") (pin "15") (pinfunction "15_15") (pintype "passive"))
      (node (ref "SIDE9") (pin "17") (pinfunction "17_17") (pintype "passive"))
      (node (ref "SIDE9") (pin "19") (pinfunction "19_19") (pintype "passive"))
      (node (ref "SIDE9") (pin "21") (pinfunction "21_21") (pintype "passive"))
      (node (ref "SIDE9") (pin "23") (pinfunction "23_23") (pintype "passive"))
      (node (ref "SIDE9") (pin "25") (pinfunction "25_25") (pintype "passive"))
      (node (ref "SIDE9") (pin "27") (pinfunction "27_27") (pintype "passive"))
      (node (ref "SIDE9") (pin "29") (pinfunction "29_29") (pintype "passive"))
      (node (ref "SIDE9") (pin "3") (pinfunction "3_3") (pintype "passive"))
      (node (ref "SIDE9") (pin "31") (pinfunction "31_31") (pintype "passive"))
      (node (ref "SIDE9") (pin "33") (pinfunction "33_33") (pintype "passive"))
      (node (ref "SIDE9") (pin "5") (pinfunction "5_5") (pintype "passive"))
      (node (ref "SIDE9") (pin "7") (pinfunction "7_7") (pintype "passive"))
      (node (ref "SIDE9") (pin "9") (pinfunction "9_9") (pintype "passive"))
    )
    (net (code "125") (name "Net-(A4G-P$2)") (class "Default")
      (node (ref "A4") (pin "D1") (pinfunction "P$2_D1") (pintype "bidirectional"))
      (node (ref "SIDE10") (pin "8") (pinfunction "8_8") (pintype "passive"))
    )
    (net (code "126") (name "Net-(A4H-P$2)") (class "Default")
      (node (ref "A4") (pin "D2") (pinfunction "P$2_D2") (pintype "bidirectional"))
      (node (ref "SIDE9") (pin "6") (pinfunction "6_6") (pintype "passive"))
    )
    (net (code "127") (name "Net-(A4I-P$2)") (class "Default")
      (node (ref "A4") (pin "E1") (pinfunction "P$2_E1") (pintype "bidirectional"))
      (node (ref "SIDE10") (pin "12") (pinfunction "12_12") (pintype "passive"))
    )
    (net (code "128") (name "Net-(A4J-P$2)") (class "Default")
      (node (ref "A4") (pin "E2") (pinfunction "P$2_E2") (pintype "bidirectional"))
      (node (ref "SIDE9") (pin "8") (pinfunction "8_8") (pintype "passive"))
    )
    (net (code "129") (name "Net-(A4K-P$2)") (class "Default")
      (node (ref "A4") (pin "F1") (pinfunction "P$2_F1") (pintype "bidirectional"))
      (node (ref "SIDE10") (pin "14") (pinfunction "14_14") (pintype "passive"))
    )
    (net (code "130") (name "Net-(A4L-P$2)") (class "Default")
      (node (ref "A4") (pin "F2") (pinfunction "P$2_F2") (pintype "bidirectional"))
      (node (ref "SIDE9") (pin "10") (pinfunction "10_10") (pintype "passive"))
    )
    (net (code "131") (name "Net-(A4M-P$2)") (class "Default")
      (node (ref "A4") (pin "H1") (pinfunction "P$2_H1") (pintype "bidirectional"))
      (node (ref "SIDE10") (pin "16") (pinfunction "16_16") (pintype "passive"))
    )
    (net (code "132") (name "Net-(A4N-P$2)") (class "Default")
      (node (ref "A4") (pin "H2") (pinfunction "P$2_H2") (pintype "bidirectional"))
      (node (ref "SIDE9") (pin "12") (pinfunction "12_12") (pintype "passive"))
    )
    (net (code "133") (name "Net-(A4O-P$2)") (class "Default")
      (node (ref "A4") (pin "J1") (pinfunction "P$2_J1") (pintype "bidirectional"))
      (node (ref "SIDE10") (pin "20") (pinfunction "20_20") (pintype "passive"))
    )
    (net (code "134") (name "Net-(A4P-P$2)") (class "Default")
      (node (ref "A4") (pin "J2") (pinfunction "P$2_J2") (pintype "bidirectional"))
      (node (ref "SIDE9") (pin "14") (pinfunction "14_14") (pintype "passive"))
    )
    (net (code "135") (name "Net-(A4Q-P$2)") (class "Default")
      (node (ref "A4") (pin "K1") (pinfunction "P$2_K1") (pintype "bidirectional"))
      (node (ref "SIDE10") (pin "18") (pinfunction "18_18") (pintype "passive"))
    )
    (net (code "136") (name "Net-(A4R-P$2)") (class "Default")
      (node (ref "A4") (pin "K2") (pinfunction "P$2_K2") (pintype "bidirectional"))
      (node (ref "SIDE9") (pin "16") (pinfunction "16_16") (pintype "passive"))
    )
    (net (code "137") (name "Net-(A4S-P$2)") (class "Default")
      (node (ref "A4") (pin "L1") (pinfunction "P$2_L1") (pintype "bidirectional"))
      (node (ref "SIDE10") (pin "24") (pinfunction "24_24") (pintype "passive"))
    )
    (net (code "138") (name "Net-(A4T-P$2)") (class "Default")
      (node (ref "A4") (pin "L2") (pinfunction "P$2_L2") (pintype "bidirectional"))
      (node (ref "SIDE9") (pin "18") (pinfunction "18_18") (pintype "passive"))
    )
    (net (code "139") (name "Net-(A4U-P$2)") (class "Default")
      (node (ref "A4") (pin "M1") (pinfunction "P$2_M1") (pintype "bidirectional"))
      (node (ref "SIDE10") (pin "28") (pinfunction "28_28") (pintype "passive"))
    )
    (net (code "140") (name "Net-(A4V-P$2)") (class "Default")
      (node (ref "A4") (pin "M2") (pinfunction "P$2_M2") (pintype "bidirectional"))
      (node (ref "SIDE9") (pin "20") (pinfunction "20_20") (pintype "passive"))
    )
    (net (code "141") (name "Net-(A4W-P$2)") (class "Default")
      (node (ref "A4") (pin "N1") (pinfunction "P$2_N1") (pintype "bidirectional"))
      (node (ref "SIDE10") (pin "22") (pinfunction "22_22") (pintype "passive"))
    )
    (net (code "142") (name "Net-(A4X-P$2)") (class "Default")
      (node (ref "A4") (pin "N2") (pinfunction "P$2_N2") (pintype "bidirectional"))
      (node (ref "SIDE9") (pin "22") (pinfunction "22_22") (pintype "passive"))
    )
    (net (code "143") (name "Net-(A4Y-P$2)") (class "Default")
      (node (ref "A4") (pin "P1") (pinfunction "P$2_P1") (pintype "bidirectional"))
      (node (ref "SIDE10") (pin "30") (pinfunction "30_30") (pintype "passive"))
    )
    (net (code "144") (name "Net-(A4Z-P$2)") (class "Default")
      (node (ref "A4") (pin "P2") (pinfunction "P$2_P2") (pintype "bidirectional"))
      (node (ref "SIDE9") (pin "24") (pinfunction "24_24") (pintype "passive"))
    )
    (net (code "145") (name "Net-(A5A-P$2)") (class "Default")
      (node (ref "A5") (pin "A1") (pinfunction "P$2_A1") (pintype "bidirectional"))
      (node (ref "SIDE1") (pin "10") (pinfunction "10_10") (pintype "passive"))
    )
    (net (code "146") (name "Net-(A5AA-P$2)") (class "Default")
      (node (ref "A5") (pin "R1") (pinfunction "P$2_R1") (pintype "bidirectional"))
      (node (ref "SIDE1") (pin "26") (pinfunction "26_26") (pintype "passive"))
    )
    (net (code "147") (name "Net-(A5AB-P$2)") (class "Default")
      (node (ref "A5") (pin "R2") (pinfunction "P$2_R2") (pintype "bidirectional"))
      (node (ref "SIDE2") (pin "26") (pinfunction "26_26") (pintype "passive"))
    )
    (net (code "148") (name "Net-(A5AC-P$2)") (class "Default")
      (node (ref "A5") (pin "S1") (pinfunction "P$2_S1") (pintype "bidirectional"))
      (node (ref "SIDE1") (pin "32") (pinfunction "32_32") (pintype "passive"))
    )
    (net (code "149") (name "Net-(A5AD-P$2)") (class "Default")
      (node (ref "A5") (pin "S2") (pinfunction "P$2_S2") (pintype "bidirectional"))
      (node (ref "SIDE2") (pin "28") (pinfunction "28_28") (pintype "passive"))
    )
    (net (code "150") (name "Net-(A5AE-P$2)") (class "Default")
      (node (ref "A5") (pin "T1") (pinfunction "P$2_T1") (pintype "bidirectional"))
      (node (ref "SIDE1") (pin "34") (pinfunction "34_34") (pintype "passive"))
    )
    (net (code "151") (name "Net-(A5AF-P$2)") (class "Default")
      (node (ref "A5") (pin "T2") (pinfunction "P$2_T2") (pintype "bidirectional"))
      (node (ref "SIDE2") (pin "30") (pinfunction "30_30") (pintype "passive"))
    )
    (net (code "152") (name "Net-(A5AG-P$2)") (class "Default")
      (node (ref "A5") (pin "U1") (pinfunction "P$2_U1") (pintype "bidirectional"))
      (node (ref "SIDE1") (pin "4") (pinfunction "4_4") (pintype "passive"))
    )
    (net (code "153") (name "Net-(A5AH-P$2)") (class "Default")
      (node (ref "A5") (pin "U2") (pinfunction "P$2_U2") (pintype "bidirectional"))
      (node (ref "SIDE2") (pin "34") (pinfunction "34_34") (pintype "passive"))
    )
    (net (code "154") (name "Net-(A5AI-P$2)") (class "Default")
      (node (ref "A5") (pin "V1") (pinfunction "P$2_V1") (pintype "bidirectional"))
      (node (ref "SIDE1") (pin "2") (pinfunction "2_2") (pintype "passive"))
    )
    (net (code "155") (name "Net-(A5AJ-P$2)") (class "Default")
      (node (ref "A5") (pin "V2") (pinfunction "P$2_V2") (pintype "bidirectional"))
      (node (ref "SIDE2") (pin "32") (pinfunction "32_32") (pintype "passive"))
    )
    (net (code "156") (name "Net-(A5B-P$2)") (class "Default")
      (node (ref "A5") (pin "A2") (pinfunction "P$2_A2") (pintype "bidirectional"))
      (node (ref "SIDE2") (pin "2") (pinfunction "2_2") (pintype "passive"))
    )
    (net (code "157") (name "Net-(A5C-P$2)") (class "Default")
      (node (ref "A5") (pin "B1") (pinfunction "P$2_B1") (pintype "bidirectional"))
      (node (ref "SIDE1") (pin "6") (pinfunction "6_6") (pintype "passive"))
    )
    (net (code "158") (name "Net-(A5D-P$2)") (class "Default")
      (node (ref "A5") (pin "B2") (pinfunction "P$2_B2") (pintype "bidirectional"))
      (node (ref "SIDE2") (pin "4") (pinfunction "4_4") (pintype "passive"))
    )
    (net (code "159") (name "Net-(A5E-P$2)") (class "Default")
      (node (ref "A5") (pin "C1") (pinfunction "P$2_C1") (pintype "bidirectional"))
      (node (ref "SIDE1") (pin "1") (pinfunction "1_1") (pintype "passive"))
      (node (ref "SIDE1") (pin "11") (pinfunction "11_11") (pintype "passive"))
      (node (ref "SIDE1") (pin "13") (pinfunction "13_13") (pintype "passive"))
      (node (ref "SIDE1") (pin "15") (pinfunction "15_15") (pintype "passive"))
      (node (ref "SIDE1") (pin "17") (pinfunction "17_17") (pintype "passive"))
      (node (ref "SIDE1") (pin "19") (pinfunction "19_19") (pintype "passive"))
      (node (ref "SIDE1") (pin "21") (pinfunction "21_21") (pintype "passive"))
      (node (ref "SIDE1") (pin "23") (pinfunction "23_23") (pintype "passive"))
      (node (ref "SIDE1") (pin "25") (pinfunction "25_25") (pintype "passive"))
      (node (ref "SIDE1") (pin "27") (pinfunction "27_27") (pintype "passive"))
      (node (ref "SIDE1") (pin "29") (pinfunction "29_29") (pintype "passive"))
      (node (ref "SIDE1") (pin "3") (pinfunction "3_3") (pintype "passive"))
      (node (ref "SIDE1") (pin "31") (pinfunction "31_31") (pintype "passive"))
      (node (ref "SIDE1") (pin "33") (pinfunction "33_33") (pintype "passive"))
      (node (ref "SIDE1") (pin "5") (pinfunction "5_5") (pintype "passive"))
      (node (ref "SIDE1") (pin "7") (pinfunction "7_7") (pintype "passive"))
      (node (ref "SIDE1") (pin "9") (pinfunction "9_9") (pintype "passive"))
    )
    (net (code "160") (name "Net-(A5F-P$2)") (class "Default")
      (node (ref "A5") (pin "C2") (pinfunction "P$2_C2") (pintype "bidirectional"))
      (node (ref "SIDE2") (pin "1") (pinfunction "1_1") (pintype "passive"))
      (node (ref "SIDE2") (pin "11") (pinfunction "11_11") (pintype "passive"))
      (node (ref "SIDE2") (pin "13") (pinfunction "13_13") (pintype "passive"))
      (node (ref "SIDE2") (pin "15") (pinfunction "15_15") (pintype "passive"))
      (node (ref "SIDE2") (pin "17") (pinfunction "17_17") (pintype "passive"))
      (node (ref "SIDE2") (pin "19") (pinfunction "19_19") (pintype "passive"))
      (node (ref "SIDE2") (pin "21") (pinfunction "21_21") (pintype "passive"))
      (node (ref "SIDE2") (pin "23") (pinfunction "23_23") (pintype "passive"))
      (node (ref "SIDE2") (pin "25") (pinfunction "25_25") (pintype "passive"))
      (node (ref "SIDE2") (pin "27") (pinfunction "27_27") (pintype "passive"))
      (node (ref "SIDE2") (pin "29") (pinfunction "29_29") (pintype "passive"))
      (node (ref "SIDE2") (pin "3") (pinfunction "3_3") (pintype "passive"))
      (node (ref "SIDE2") (pin "31") (pinfunction "31_31") (pintype "passive"))
      (node (ref "SIDE2") (pin "33") (pinfunction "33_33") (pintype "passive"))
      (node (ref "SIDE2") (pin "5") (pinfunction "5_5") (pintype "passive"))
      (node (ref "SIDE2") (pin "7") (pinfunction "7_7") (pintype "passive"))
      (node (ref "SIDE2") (pin "9") (pinfunction "9_9") (pintype "passive"))
    )
    (net (code "161") (name "Net-(A5G-P$2)") (class "Default")
      (node (ref "A5") (pin "D1") (pinfunction "P$2_D1") (pintype "bidirectional"))
      (node (ref "SIDE1") (pin "8") (pinfunction "8_8") (pintype "passive"))
    )
    (net (code "162") (name "Net-(A5H-P$2)") (class "Default")
      (node (ref "A5") (pin "D2") (pinfunction "P$2_D2") (pintype "bidirectional"))
      (node (ref "SIDE2") (pin "6") (pinfunction "6_6") (pintype "passive"))
    )
    (net (code "163") (name "Net-(A5I-P$2)") (class "Default")
      (node (ref "A5") (pin "E1") (pinfunction "P$2_E1") (pintype "bidirectional"))
      (node (ref "SIDE1") (pin "12") (pinfunction "12_12") (pintype "passive"))
    )
    (net (code "164") (name "Net-(A5J-P$2)") (class "Default")
      (node (ref "A5") (pin "E2") (pinfunction "P$2_E2") (pintype "bidirectional"))
      (node (ref "SIDE2") (pin "8") (pinfunction "8_8") (pintype "passive"))
    )
    (net (code "165") (name "Net-(A5K-P$2)") (class "Default")
      (node (ref "A5") (pin "F1") (pinfunction "P$2_F1") (pintype "bidirectional"))
      (node (ref "SIDE1") (pin "14") (pinfunction "14_14") (pintype "passive"))
    )
    (net (code "166") (name "Net-(A5L-P$2)") (class "Default")
      (node (ref "A5") (pin "F2") (pinfunction "P$2_F2") (pintype "bidirectional"))
      (node (ref "SIDE2") (pin "10") (pinfunction "10_10") (pintype "passive"))
    )
    (net (code "167") (name "Net-(A5M-P$2)") (class "Default")
      (node (ref "A5") (pin "H1") (pinfunction "P$2_H1") (pintype "bidirectional"))
      (node (ref "SIDE1") (pin "16") (pinfunction "16_16") (pintype "passive"))
    )
    (net (code "168") (name "Net-(A5N-P$2)") (class "Default")
      (node (ref "A5") (pin "H2") (pinfunction "P$2_H2") (pintype "bidirectional"))
      (node (ref "SIDE2") (pin "12") (pinfunction "12_12") (pintype "passive"))
    )
    (net (code "169") (name "Net-(A5O-P$2)") (class "Default")
      (node (ref "A5") (pin "J1") (pinfunction "P$2_J1") (pintype "bidirectional"))
      (node (ref "SIDE1") (pin "20") (pinfunction "20_20") (pintype "passive"))
    )
    (net (code "170") (name "Net-(A5P-P$2)") (class "Default")
      (node (ref "A5") (pin "J2") (pinfunction "P$2_J2") (pintype "bidirectional"))
      (node (ref "SIDE2") (pin "14") (pinfunction "14_14") (pintype "passive"))
    )
    (net (code "171") (name "Net-(A5Q-P$2)") (class "Default")
      (node (ref "A5") (pin "K1") (pinfunction "P$2_K1") (pintype "bidirectional"))
      (node (ref "SIDE1") (pin "18") (pinfunction "18_18") (pintype "passive"))
    )
    (net (code "172") (name "Net-(A5R-P$2)") (class "Default")
      (node (ref "A5") (pin "K2") (pinfunction "P$2_K2") (pintype "bidirectional"))
      (node (ref "SIDE2") (pin "16") (pinfunction "16_16") (pintype "passive"))
    )
    (net (code "173") (name "Net-(A5S-P$2)") (class "Default")
      (node (ref "A5") (pin "L1") (pinfunction "P$2_L1") (pintype "bidirectional"))
      (node (ref "SIDE1") (pin "24") (pinfunction "24_24") (pintype "passive"))
    )
    (net (code "174") (name "Net-(A5T-P$2)") (class "Default")
      (node (ref "A5") (pin "L2") (pinfunction "P$2_L2") (pintype "bidirectional"))
      (node (ref "SIDE2") (pin "18") (pinfunction "18_18") (pintype "passive"))
    )
    (net (code "175") (name "Net-(A5U-P$2)") (class "Default")
      (node (ref "A5") (pin "M1") (pinfunction "P$2_M1") (pintype "bidirectional"))
      (node (ref "SIDE1") (pin "28") (pinfunction "28_28") (pintype "passive"))
    )
    (net (code "176") (name "Net-(A5V-P$2)") (class "Default")
      (node (ref "A5") (pin "M2") (pinfunction "P$2_M2") (pintype "bidirectional"))
      (node (ref "SIDE2") (pin "20") (pinfunction "20_20") (pintype "passive"))
    )
    (net (code "177") (name "Net-(A5W-P$2)") (class "Default")
      (node (ref "A5") (pin "N1") (pinfunction "P$2_N1") (pintype "bidirectional"))
      (node (ref "SIDE1") (pin "22") (pinfunction "22_22") (pintype "passive"))
    )
    (net (code "178") (name "Net-(A5X-P$2)") (class "Default")
      (node (ref "A5") (pin "N2") (pinfunction "P$2_N2") (pintype "bidirectional"))
      (node (ref "SIDE2") (pin "22") (pinfunction "22_22") (pintype "passive"))
    )
    (net (code "179") (name "Net-(A5Y-P$2)") (class "Default")
      (node (ref "A5") (pin "P1") (pinfunction "P$2_P1") (pintype "bidirectional"))
      (node (ref "SIDE1") (pin "30") (pinfunction "30_30") (pintype "passive"))
    )
    (net (code "180") (name "Net-(A5Z-P$2)") (class "Default")
      (node (ref "A5") (pin "P2") (pinfunction "P$2_P2") (pintype "bidirectional"))
      (node (ref "SIDE2") (pin "24") (pinfunction "24_24") (pintype "passive"))
    )
    (net (code "181") (name "Net-(A6A-P$2)") (class "Default")
      (node (ref "A6") (pin "A1") (pinfunction "P$2_A1") (pintype "bidirectional"))
      (node (ref "SIDE12") (pin "10") (pinfunction "10_10") (pintype "passive"))
    )
    (net (code "182") (name "Net-(A6AA-P$2)") (class "Default")
      (node (ref "A6") (pin "R1") (pinfunction "P$2_R1") (pintype "bidirectional"))
      (node (ref "SIDE12") (pin "26") (pinfunction "26_26") (pintype "passive"))
    )
    (net (code "183") (name "Net-(A6AB-P$2)") (class "Default")
      (node (ref "A6") (pin "R2") (pinfunction "P$2_R2") (pintype "bidirectional"))
      (node (ref "SIDE11") (pin "26") (pinfunction "26_26") (pintype "passive"))
    )
    (net (code "184") (name "Net-(A6AC-P$2)") (class "Default")
      (node (ref "A6") (pin "S1") (pinfunction "P$2_S1") (pintype "bidirectional"))
      (node (ref "SIDE12") (pin "32") (pinfunction "32_32") (pintype "passive"))
    )
    (net (code "185") (name "Net-(A6AD-P$2)") (class "Default")
      (node (ref "A6") (pin "S2") (pinfunction "P$2_S2") (pintype "bidirectional"))
      (node (ref "SIDE11") (pin "28") (pinfunction "28_28") (pintype "passive"))
    )
    (net (code "186") (name "Net-(A6AE-P$2)") (class "Default")
      (node (ref "A6") (pin "T1") (pinfunction "P$2_T1") (pintype "bidirectional"))
      (node (ref "SIDE12") (pin "34") (pinfunction "34_34") (pintype "passive"))
    )
    (net (code "187") (name "Net-(A6AF-P$2)") (class "Default")
      (node (ref "A6") (pin "T2") (pinfunction "P$2_T2") (pintype "bidirectional"))
      (node (ref "SIDE11") (pin "30") (pinfunction "30_30") (pintype "passive"))
    )
    (net (code "188") (name "Net-(A6AG-P$2)") (class "Default")
      (node (ref "A6") (pin "U1") (pinfunction "P$2_U1") (pintype "bidirectional"))
      (node (ref "SIDE12") (pin "4") (pinfunction "4_4") (pintype "passive"))
    )
    (net (code "189") (name "Net-(A6AH-P$2)") (class "Default")
      (node (ref "A6") (pin "U2") (pinfunction "P$2_U2") (pintype "bidirectional"))
      (node (ref "SIDE11") (pin "34") (pinfunction "34_34") (pintype "passive"))
    )
    (net (code "190") (name "Net-(A6AI-P$2)") (class "Default")
      (node (ref "A6") (pin "V1") (pinfunction "P$2_V1") (pintype "bidirectional"))
      (node (ref "SIDE12") (pin "2") (pinfunction "2_2") (pintype "passive"))
    )
    (net (code "191") (name "Net-(A6AJ-P$2)") (class "Default")
      (node (ref "A6") (pin "V2") (pinfunction "P$2_V2") (pintype "bidirectional"))
      (node (ref "SIDE11") (pin "32") (pinfunction "32_32") (pintype "passive"))
    )
    (net (code "192") (name "Net-(A6B-P$2)") (class "Default")
      (node (ref "A6") (pin "A2") (pinfunction "P$2_A2") (pintype "bidirectional"))
      (node (ref "SIDE11") (pin "2") (pinfunction "2_2") (pintype "passive"))
    )
    (net (code "193") (name "Net-(A6C-P$2)") (class "Default")
      (node (ref "A6") (pin "B1") (pinfunction "P$2_B1") (pintype "bidirectional"))
      (node (ref "SIDE12") (pin "6") (pinfunction "6_6") (pintype "passive"))
    )
    (net (code "194") (name "Net-(A6D-P$2)") (class "Default")
      (node (ref "A6") (pin "B2") (pinfunction "P$2_B2") (pintype "bidirectional"))
      (node (ref "SIDE11") (pin "4") (pinfunction "4_4") (pintype "passive"))
    )
    (net (code "195") (name "Net-(A6E-P$2)") (class "Default")
      (node (ref "A6") (pin "C1") (pinfunction "P$2_C1") (pintype "bidirectional"))
      (node (ref "SIDE12") (pin "1") (pinfunction "1_1") (pintype "passive"))
      (node (ref "SIDE12") (pin "11") (pinfunction "11_11") (pintype "passive"))
      (node (ref "SIDE12") (pin "13") (pinfunction "13_13") (pintype "passive"))
      (node (ref "SIDE12") (pin "15") (pinfunction "15_15") (pintype "passive"))
      (node (ref "SIDE12") (pin "17") (pinfunction "17_17") (pintype "passive"))
      (node (ref "SIDE12") (pin "19") (pinfunction "19_19") (pintype "passive"))
      (node (ref "SIDE12") (pin "21") (pinfunction "21_21") (pintype "passive"))
      (node (ref "SIDE12") (pin "23") (pinfunction "23_23") (pintype "passive"))
      (node (ref "SIDE12") (pin "25") (pinfunction "25_25") (pintype "passive"))
      (node (ref "SIDE12") (pin "27") (pinfunction "27_27") (pintype "passive"))
      (node (ref "SIDE12") (pin "29") (pinfunction "29_29") (pintype "passive"))
      (node (ref "SIDE12") (pin "3") (pinfunction "3_3") (pintype "passive"))
      (node (ref "SIDE12") (pin "31") (pinfunction "31_31") (pintype "passive"))
      (node (ref "SIDE12") (pin "33") (pinfunction "33_33") (pintype "passive"))
      (node (ref "SIDE12") (pin "5") (pinfunction "5_5") (pintype "passive"))
      (node (ref "SIDE12") (pin "7") (pinfunction "7_7") (pintype "passive"))
      (node (ref "SIDE12") (pin "9") (pinfunction "9_9") (pintype "passive"))
    )
    (net (code "196") (name "Net-(A6F-P$2)") (class "Default")
      (node (ref "A6") (pin "C2") (pinfunction "P$2_C2") (pintype "bidirectional"))
      (node (ref "SIDE11") (pin "1") (pinfunction "1_1") (pintype "passive"))
      (node (ref "SIDE11") (pin "11") (pinfunction "11_11") (pintype "passive"))
      (node (ref "SIDE11") (pin "13") (pinfunction "13_13") (pintype "passive"))
      (node (ref "SIDE11") (pin "15") (pinfunction "15_15") (pintype "passive"))
      (node (ref "SIDE11") (pin "17") (pinfunction "17_17") (pintype "passive"))
      (node (ref "SIDE11") (pin "19") (pinfunction "19_19") (pintype "passive"))
      (node (ref "SIDE11") (pin "21") (pinfunction "21_21") (pintype "passive"))
      (node (ref "SIDE11") (pin "23") (pinfunction "23_23") (pintype "passive"))
      (node (ref "SIDE11") (pin "25") (pinfunction "25_25") (pintype "passive"))
      (node (ref "SIDE11") (pin "27") (pinfunction "27_27") (pintype "passive"))
      (node (ref "SIDE11") (pin "29") (pinfunction "29_29") (pintype "passive"))
      (node (ref "SIDE11") (pin "3") (pinfunction "3_3") (pintype "passive"))
      (node (ref "SIDE11") (pin "31") (pinfunction "31_31") (pintype "passive"))
      (node (ref "SIDE11") (pin "33") (pinfunction "33_33") (pintype "passive"))
      (node (ref "SIDE11") (pin "5") (pinfunction "5_5") (pintype "passive"))
      (node (ref "SIDE11") (pin "7") (pinfunction "7_7") (pintype "passive"))
      (node (ref "SIDE11") (pin "9") (pinfunction "9_9") (pintype "passive"))
    )
    (net (code "197") (name "Net-(A6G-P$2)") (class "Default")
      (node (ref "A6") (pin "D1") (pinfunction "P$2_D1") (pintype "bidirectional"))
      (node (ref "SIDE12") (pin "8") (pinfunction "8_8") (pintype "passive"))
    )
    (net (code "198") (name "Net-(A6H-P$2)") (class "Default")
      (node (ref "A6") (pin "D2") (pinfunction "P$2_D2") (pintype "bidirectional"))
      (node (ref "SIDE11") (pin "6") (pinfunction "6_6") (pintype "passive"))
    )
    (net (code "199") (name "Net-(A6I-P$2)") (class "Default")
      (node (ref "A6") (pin "E1") (pinfunction "P$2_E1") (pintype "bidirectional"))
      (node (ref "SIDE12") (pin "12") (pinfunction "12_12") (pintype "passive"))
    )
    (net (code "200") (name "Net-(A6J-P$2)") (class "Default")
      (node (ref "A6") (pin "E2") (pinfunction "P$2_E2") (pintype "bidirectional"))
      (node (ref "SIDE11") (pin "8") (pinfunction "8_8") (pintype "passive"))
    )
    (net (code "201") (name "Net-(A6K-P$2)") (class "Default")
      (node (ref "A6") (pin "F1") (pinfunction "P$2_F1") (pintype "bidirectional"))
      (node (ref "SIDE12") (pin "14") (pinfunction "14_14") (pintype "passive"))
    )
    (net (code "202") (name "Net-(A6L-P$2)") (class "Default")
      (node (ref "A6") (pin "F2") (pinfunction "P$2_F2") (pintype "bidirectional"))
      (node (ref "SIDE11") (pin "10") (pinfunction "10_10") (pintype "passive"))
    )
    (net (code "203") (name "Net-(A6M-P$2)") (class "Default")
      (node (ref "A6") (pin "H1") (pinfunction "P$2_H1") (pintype "bidirectional"))
      (node (ref "SIDE12") (pin "16") (pinfunction "16_16") (pintype "passive"))
    )
    (net (code "204") (name "Net-(A6N-P$2)") (class "Default")
      (node (ref "A6") (pin "H2") (pinfunction "P$2_H2") (pintype "bidirectional"))
      (node (ref "SIDE11") (pin "12") (pinfunction "12_12") (pintype "passive"))
    )
    (net (code "205") (name "Net-(A6O-P$2)") (class "Default")
      (node (ref "A6") (pin "J1") (pinfunction "P$2_J1") (pintype "bidirectional"))
      (node (ref "SIDE12") (pin "20") (pinfunction "20_20") (pintype "passive"))
    )
    (net (code "206") (name "Net-(A6P-P$2)") (class "Default")
      (node (ref "A6") (pin "J2") (pinfunction "P$2_J2") (pintype "bidirectional"))
      (node (ref "SIDE11") (pin "14") (pinfunction "14_14") (pintype "passive"))
    )
    (net (code "207") (name "Net-(A6Q-P$2)") (class "Default")
      (node (ref "A6") (pin "K1") (pinfunction "P$2_K1") (pintype "bidirectional"))
      (node (ref "SIDE12") (pin "18") (pinfunction "18_18") (pintype "passive"))
    )
    (net (code "208") (name "Net-(A6R-P$2)") (class "Default")
      (node (ref "A6") (pin "K2") (pinfunction "P$2_K2") (pintype "bidirectional"))
      (node (ref "SIDE11") (pin "16") (pinfunction "16_16") (pintype "passive"))
    )
    (net (code "209") (name "Net-(A6S-P$2)") (class "Default")
      (node (ref "A6") (pin "L1") (pinfunction "P$2_L1") (pintype "bidirectional"))
      (node (ref "SIDE12") (pin "24") (pinfunction "24_24") (pintype "passive"))
    )
    (net (code "210") (name "Net-(A6T-P$2)") (class "Default")
      (node (ref "A6") (pin "L2") (pinfunction "P$2_L2") (pintype "bidirectional"))
      (node (ref "SIDE11") (pin "18") (pinfunction "18_18") (pintype "passive"))
    )
    (net (code "211") (name "Net-(A6U-P$2)") (class "Default")
      (node (ref "A6") (pin "M1") (pinfunction "P$2_M1") (pintype "bidirectional"))
      (node (ref "SIDE12") (pin "28") (pinfunction "28_28") (pintype "passive"))
    )
    (net (code "212") (name "Net-(A6V-P$2)") (class "Default")
      (node (ref "A6") (pin "M2") (pinfunction "P$2_M2") (pintype "bidirectional"))
      (node (ref "SIDE11") (pin "20") (pinfunction "20_20") (pintype "passive"))
    )
    (net (code "213") (name "Net-(A6W-P$2)") (class "Default")
      (node (ref "A6") (pin "N1") (pinfunction "P$2_N1") (pintype "bidirectional"))
      (node (ref "SIDE12") (pin "22") (pinfunction "22_22") (pintype "passive"))
    )
    (net (code "214") (name "Net-(A6X-P$2)") (class "Default")
      (node (ref "A6") (pin "N2") (pinfunction "P$2_N2") (pintype "bidirectional"))
      (node (ref "SIDE11") (pin "22") (pinfunction "22_22") (pintype "passive"))
    )
    (net (code "215") (name "Net-(A6Y-P$2)") (class "Default")
      (node (ref "A6") (pin "P1") (pinfunction "P$2_P1") (pintype "bidirectional"))
      (node (ref "SIDE12") (pin "30") (pinfunction "30_30") (pintype "passive"))
    )
    (net (code "216") (name "Net-(A6Z-P$2)") (class "Default")
      (node (ref "A6") (pin "P2") (pinfunction "P$2_P2") (pintype "bidirectional"))
      (node (ref "SIDE11") (pin "24") (pinfunction "24_24") (pintype "passive"))
    )
    (net (code "217") (name "Net-(A7A-P$2)") (class "Default")
      (node (ref "A7") (pin "A1") (pinfunction "P$2_A1") (pintype "bidirectional"))
      (node (ref "SIDE14") (pin "10") (pinfunction "10_10") (pintype "passive"))
    )
    (net (code "218") (name "Net-(A7AA-P$2)") (class "Default")
      (node (ref "A7") (pin "R1") (pinfunction "P$2_R1") (pintype "bidirectional"))
      (node (ref "SIDE14") (pin "26") (pinfunction "26_26") (pintype "passive"))
    )
    (net (code "219") (name "Net-(A7AB-P$2)") (class "Default")
      (node (ref "A7") (pin "R2") (pinfunction "P$2_R2") (pintype "bidirectional"))
      (node (ref "SIDE13") (pin "26") (pinfunction "26_26") (pintype "passive"))
    )
    (net (code "220") (name "Net-(A7AC-P$2)") (class "Default")
      (node (ref "A7") (pin "S1") (pinfunction "P$2_S1") (pintype "bidirectional"))
      (node (ref "SIDE14") (pin "32") (pinfunction "32_32") (pintype "passive"))
    )
    (net (code "221") (name "Net-(A7AD-P$2)") (class "Default")
      (node (ref "A7") (pin "S2") (pinfunction "P$2_S2") (pintype "bidirectional"))
      (node (ref "SIDE13") (pin "28") (pinfunction "28_28") (pintype "passive"))
    )
    (net (code "222") (name "Net-(A7AE-P$2)") (class "Default")
      (node (ref "A7") (pin "T1") (pinfunction "P$2_T1") (pintype "bidirectional"))
      (node (ref "SIDE14") (pin "34") (pinfunction "34_34") (pintype "passive"))
    )
    (net (code "223") (name "Net-(A7AF-P$2)") (class "Default")
      (node (ref "A7") (pin "T2") (pinfunction "P$2_T2") (pintype "bidirectional"))
      (node (ref "SIDE13") (pin "30") (pinfunction "30_30") (pintype "passive"))
    )
    (net (code "224") (name "Net-(A7AG-P$2)") (class "Default")
      (node (ref "A7") (pin "U1") (pinfunction "P$2_U1") (pintype "bidirectional"))
      (node (ref "SIDE14") (pin "4") (pinfunction "4_4") (pintype "passive"))
    )
    (net (code "225") (name "Net-(A7AH-P$2)") (class "Default")
      (node (ref "A7") (pin "U2") (pinfunction "P$2_U2") (pintype "bidirectional"))
      (node (ref "SIDE13") (pin "34") (pinfunction "34_34") (pintype "passive"))
    )
    (net (code "226") (name "Net-(A7AI-P$2)") (class "Default")
      (node (ref "A7") (pin "V1") (pinfunction "P$2_V1") (pintype "bidirectional"))
      (node (ref "SIDE14") (pin "2") (pinfunction "2_2") (pintype "passive"))
    )
    (net (code "227") (name "Net-(A7AJ-P$2)") (class "Default")
      (node (ref "A7") (pin "V2") (pinfunction "P$2_V2") (pintype "bidirectional"))
      (node (ref "SIDE13") (pin "32") (pinfunction "32_32") (pintype "passive"))
    )
    (net (code "228") (name "Net-(A7B-P$2)") (class "Default")
      (node (ref "A7") (pin "A2") (pinfunction "P$2_A2") (pintype "bidirectional"))
      (node (ref "SIDE13") (pin "2") (pinfunction "2_2") (pintype "passive"))
    )
    (net (code "229") (name "Net-(A7C-P$2)") (class "Default")
      (node (ref "A7") (pin "B1") (pinfunction "P$2_B1") (pintype "bidirectional"))
      (node (ref "SIDE14") (pin "6") (pinfunction "6_6") (pintype "passive"))
    )
    (net (code "230") (name "Net-(A7D-P$2)") (class "Default")
      (node (ref "A7") (pin "B2") (pinfunction "P$2_B2") (pintype "bidirectional"))
      (node (ref "SIDE13") (pin "4") (pinfunction "4_4") (pintype "passive"))
    )
    (net (code "231") (name "Net-(A7E-P$2)") (class "Default")
      (node (ref "A7") (pin "C1") (pinfunction "P$2_C1") (pintype "bidirectional"))
      (node (ref "SIDE14") (pin "1") (pinfunction "1_1") (pintype "passive"))
      (node (ref "SIDE14") (pin "11") (pinfunction "11_11") (pintype "passive"))
      (node (ref "SIDE14") (pin "13") (pinfunction "13_13") (pintype "passive"))
      (node (ref "SIDE14") (pin "15") (pinfunction "15_15") (pintype "passive"))
      (node (ref "SIDE14") (pin "17") (pinfunction "17_17") (pintype "passive"))
      (node (ref "SIDE14") (pin "19") (pinfunction "19_19") (pintype "passive"))
      (node (ref "SIDE14") (pin "21") (pinfunction "21_21") (pintype "passive"))
      (node (ref "SIDE14") (pin "23") (pinfunction "23_23") (pintype "passive"))
      (node (ref "SIDE14") (pin "25") (pinfunction "25_25") (pintype "passive"))
      (node (ref "SIDE14") (pin "27") (pinfunction "27_27") (pintype "passive"))
      (node (ref "SIDE14") (pin "29") (pinfunction "29_29") (pintype "passive"))
      (node (ref "SIDE14") (pin "3") (pinfunction "3_3") (pintype "passive"))
      (node (ref "SIDE14") (pin "31") (pinfunction "31_31") (pintype "passive"))
      (node (ref "SIDE14") (pin "33") (pinfunction "33_33") (pintype "passive"))
      (node (ref "SIDE14") (pin "5") (pinfunction "5_5") (pintype "passive"))
      (node (ref "SIDE14") (pin "7") (pinfunction "7_7") (pintype "passive"))
      (node (ref "SIDE14") (pin "9") (pinfunction "9_9") (pintype "passive"))
    )
    (net (code "232") (name "Net-(A7F-P$2)") (class "Default")
      (node (ref "A7") (pin "C2") (pinfunction "P$2_C2") (pintype "bidirectional"))
      (node (ref "SIDE13") (pin "1") (pinfunction "1_1") (pintype "passive"))
      (node (ref "SIDE13") (pin "11") (pinfunction "11_11") (pintype "passive"))
      (node (ref "SIDE13") (pin "13") (pinfunction "13_13") (pintype "passive"))
      (node (ref "SIDE13") (pin "15") (pinfunction "15_15") (pintype "passive"))
      (node (ref "SIDE13") (pin "17") (pinfunction "17_17") (pintype "passive"))
      (node (ref "SIDE13") (pin "19") (pinfunction "19_19") (pintype "passive"))
      (node (ref "SIDE13") (pin "21") (pinfunction "21_21") (pintype "passive"))
      (node (ref "SIDE13") (pin "23") (pinfunction "23_23") (pintype "passive"))
      (node (ref "SIDE13") (pin "25") (pinfunction "25_25") (pintype "passive"))
      (node (ref "SIDE13") (pin "27") (pinfunction "27_27") (pintype "passive"))
      (node (ref "SIDE13") (pin "29") (pinfunction "29_29") (pintype "passive"))
      (node (ref "SIDE13") (pin "3") (pinfunction "3_3") (pintype "passive"))
      (node (ref "SIDE13") (pin "31") (pinfunction "31_31") (pintype "passive"))
      (node (ref "SIDE13") (pin "33") (pinfunction "33_33") (pintype "passive"))
      (node (ref "SIDE13") (pin "5") (pinfunction "5_5") (pintype "passive"))
      (node (ref "SIDE13") (pin "7") (pinfunction "7_7") (pintype "passive"))
      (node (ref "SIDE13") (pin "9") (pinfunction "9_9") (pintype "passive"))
    )
    (net (code "233") (name "Net-(A7G-P$2)") (class "Default")
      (node (ref "A7") (pin "D1") (pinfunction "P$2_D1") (pintype "bidirectional"))
      (node (ref "SIDE14") (pin "8") (pinfunction "8_8") (pintype "passive"))
    )
    (net (code "234") (name "Net-(A7H-P$2)") (class "Default")
      (node (ref "A7") (pin "D2") (pinfunction "P$2_D2") (pintype "bidirectional"))
      (node (ref "SIDE13") (pin "6") (pinfunction "6_6") (pintype "passive"))
    )
    (net (code "235") (name "Net-(A7I-P$2)") (class "Default")
      (node (ref "A7") (pin "E1") (pinfunction "P$2_E1") (pintype "bidirectional"))
      (node (ref "SIDE14") (pin "12") (pinfunction "12_12") (pintype "passive"))
    )
    (net (code "236") (name "Net-(A7J-P$2)") (class "Default")
      (node (ref "A7") (pin "E2") (pinfunction "P$2_E2") (pintype "bidirectional"))
      (node (ref "SIDE13") (pin "8") (pinfunction "8_8") (pintype "passive"))
    )
    (net (code "237") (name "Net-(A7K-P$2)") (class "Default")
      (node (ref "A7") (pin "F1") (pinfunction "P$2_F1") (pintype "bidirectional"))
      (node (ref "SIDE14") (pin "14") (pinfunction "14_14") (pintype "passive"))
    )
    (net (code "238") (name "Net-(A7L-P$2)") (class "Default")
      (node (ref "A7") (pin "F2") (pinfunction "P$2_F2") (pintype "bidirectional"))
      (node (ref "SIDE13") (pin "10") (pinfunction "10_10") (pintype "passive"))
    )
    (net (code "239") (name "Net-(A7M-P$2)") (class "Default")
      (node (ref "A7") (pin "H1") (pinfunction "P$2_H1") (pintype "bidirectional"))
      (node (ref "SIDE14") (pin "16") (pinfunction "16_16") (pintype "passive"))
    )
    (net (code "240") (name "Net-(A7N-P$2)") (class "Default")
      (node (ref "A7") (pin "H2") (pinfunction "P$2_H2") (pintype "bidirectional"))
      (node (ref "SIDE13") (pin "12") (pinfunction "12_12") (pintype "passive"))
    )
    (net (code "241") (name "Net-(A7O-P$2)") (class "Default")
      (node (ref "A7") (pin "J1") (pinfunction "P$2_J1") (pintype "bidirectional"))
      (node (ref "SIDE14") (pin "20") (pinfunction "20_20") (pintype "passive"))
    )
    (net (code "242") (name "Net-(A7P-P$2)") (class "Default")
      (node (ref "A7") (pin "J2") (pinfunction "P$2_J2") (pintype "bidirectional"))
      (node (ref "SIDE13") (pin "14") (pinfunction "14_14") (pintype "passive"))
    )
    (net (code "243") (name "Net-(A7Q-P$2)") (class "Default")
      (node (ref "A7") (pin "K1") (pinfunction "P$2_K1") (pintype "bidirectional"))
      (node (ref "SIDE14") (pin "18") (pinfunction "18_18") (pintype "passive"))
    )
    (net (code "244") (name "Net-(A7R-P$2)") (class "Default")
      (node (ref "A7") (pin "K2") (pinfunction "P$2_K2") (pintype "bidirectional"))
      (node (ref "SIDE13") (pin "16") (pinfunction "16_16") (pintype "passive"))
    )
    (net (code "245") (name "Net-(A7S-P$2)") (class "Default")
      (node (ref "A7") (pin "L1") (pinfunction "P$2_L1") (pintype "bidirectional"))
      (node (ref "SIDE14") (pin "24") (pinfunction "24_24") (pintype "passive"))
    )
    (net (code "246") (name "Net-(A7T-P$2)") (class "Default")
      (node (ref "A7") (pin "L2") (pinfunction "P$2_L2") (pintype "bidirectional"))
      (node (ref "SIDE13") (pin "18") (pinfunction "18_18") (pintype "passive"))
    )
    (net (code "247") (name "Net-(A7U-P$2)") (class "Default")
      (node (ref "A7") (pin "M1") (pinfunction "P$2_M1") (pintype "bidirectional"))
      (node (ref "SIDE14") (pin "28") (pinfunction "28_28") (pintype "passive"))
    )
    (net (code "248") (name "Net-(A7V-P$2)") (class "Default")
      (node (ref "A7") (pin "M2") (pinfunction "P$2_M2") (pintype "bidirectional"))
      (node (ref "SIDE13") (pin "20") (pinfunction "20_20") (pintype "passive"))
    )
    (net (code "249") (name "Net-(A7W-P$2)") (class "Default")
      (node (ref "A7") (pin "N1") (pinfunction "P$2_N1") (pintype "bidirectional"))
      (node (ref "SIDE14") (pin "22") (pinfunction "22_22") (pintype "passive"))
    )
    (net (code "250") (name "Net-(A7X-P$2)") (class "Default")
      (node (ref "A7") (pin "N2") (pinfunction "P$2_N2") (pintype "bidirectional"))
      (node (ref "SIDE13") (pin "22") (pinfunction "22_22") (pintype "passive"))
    )
    (net (code "251") (name "Net-(A7Y-P$2)") (class "Default")
      (node (ref "A7") (pin "P1") (pinfunction "P$2_P1") (pintype "bidirectional"))
      (node (ref "SIDE14") (pin "30") (pinfunction "30_30") (pintype "passive"))
    )
    (net (code "252") (name "Net-(A7Z-P$2)") (class "Default")
      (node (ref "A7") (pin "P2") (pinfunction "P$2_P2") (pintype "bidirectional"))
      (node (ref "SIDE13") (pin "24") (pinfunction "24_24") (pintype "passive"))
    )
    (net (code "253") (name "Net-(A8A-P$2)") (class "Default")
      (node (ref "A8") (pin "A1") (pinfunction "P$2_A1") (pintype "bidirectional"))
      (node (ref "SIDE16") (pin "10") (pinfunction "10_10") (pintype "passive"))
    )
    (net (code "254") (name "Net-(A8AA-P$2)") (class "Default")
      (node (ref "A8") (pin "R1") (pinfunction "P$2_R1") (pintype "bidirectional"))
      (node (ref "SIDE16") (pin "26") (pinfunction "26_26") (pintype "passive"))
    )
    (net (code "255") (name "Net-(A8AB-P$2)") (class "Default")
      (node (ref "A8") (pin "R2") (pinfunction "P$2_R2") (pintype "bidirectional"))
      (node (ref "SIDE15") (pin "26") (pinfunction "26_26") (pintype "passive"))
    )
    (net (code "256") (name "Net-(A8AC-P$2)") (class "Default")
      (node (ref "A8") (pin "S1") (pinfunction "P$2_S1") (pintype "bidirectional"))
      (node (ref "SIDE16") (pin "32") (pinfunction "32_32") (pintype "passive"))
    )
    (net (code "257") (name "Net-(A8AD-P$2)") (class "Default")
      (node (ref "A8") (pin "S2") (pinfunction "P$2_S2") (pintype "bidirectional"))
      (node (ref "SIDE15") (pin "28") (pinfunction "28_28") (pintype "passive"))
    )
    (net (code "258") (name "Net-(A8AE-P$2)") (class "Default")
      (node (ref "A8") (pin "T1") (pinfunction "P$2_T1") (pintype "bidirectional"))
      (node (ref "SIDE16") (pin "34") (pinfunction "34_34") (pintype "passive"))
    )
    (net (code "259") (name "Net-(A8AF-P$2)") (class "Default")
      (node (ref "A8") (pin "T2") (pinfunction "P$2_T2") (pintype "bidirectional"))
      (node (ref "SIDE15") (pin "30") (pinfunction "30_30") (pintype "passive"))
    )
    (net (code "260") (name "Net-(A8AG-P$2)") (class "Default")
      (node (ref "A8") (pin "U1") (pinfunction "P$2_U1") (pintype "bidirectional"))
      (node (ref "SIDE16") (pin "4") (pinfunction "4_4") (pintype "passive"))
    )
    (net (code "261") (name "Net-(A8AH-P$2)") (class "Default")
      (node (ref "A8") (pin "U2") (pinfunction "P$2_U2") (pintype "bidirectional"))
      (node (ref "SIDE15") (pin "34") (pinfunction "34_34") (pintype "passive"))
    )
    (net (code "262") (name "Net-(A8AI-P$2)") (class "Default")
      (node (ref "A8") (pin "V1") (pinfunction "P$2_V1") (pintype "bidirectional"))
      (node (ref "SIDE16") (pin "2") (pinfunction "2_2") (pintype "passive"))
    )
    (net (code "263") (name "Net-(A8AJ-P$2)") (class "Default")
      (node (ref "A8") (pin "V2") (pinfunction "P$2_V2") (pintype "bidirectional"))
      (node (ref "SIDE15") (pin "32") (pinfunction "32_32") (pintype "passive"))
    )
    (net (code "264") (name "Net-(A8B-P$2)") (class "Default")
      (node (ref "A8") (pin "A2") (pinfunction "P$2_A2") (pintype "bidirectional"))
      (node (ref "SIDE15") (pin "2") (pinfunction "2_2") (pintype "passive"))
    )
    (net (code "265") (name "Net-(A8C-P$2)") (class "Default")
      (node (ref "A8") (pin "B1") (pinfunction "P$2_B1") (pintype "bidirectional"))
      (node (ref "SIDE16") (pin "6") (pinfunction "6_6") (pintype "passive"))
    )
    (net (code "266") (name "Net-(A8D-P$2)") (class "Default")
      (node (ref "A8") (pin "B2") (pinfunction "P$2_B2") (pintype "bidirectional"))
      (node (ref "SIDE15") (pin "4") (pinfunction "4_4") (pintype "passive"))
    )
    (net (code "267") (name "Net-(A8E-P$2)") (class "Default")
      (node (ref "A8") (pin "C1") (pinfunction "P$2_C1") (pintype "bidirectional"))
      (node (ref "SIDE16") (pin "1") (pinfunction "1_1") (pintype "passive"))
      (node (ref "SIDE16") (pin "11") (pinfunction "11_11") (pintype "passive"))
      (node (ref "SIDE16") (pin "13") (pinfunction "13_13") (pintype "passive"))
      (node (ref "SIDE16") (pin "15") (pinfunction "15_15") (pintype "passive"))
      (node (ref "SIDE16") (pin "17") (pinfunction "17_17") (pintype "passive"))
      (node (ref "SIDE16") (pin "19") (pinfunction "19_19") (pintype "passive"))
      (node (ref "SIDE16") (pin "21") (pinfunction "21_21") (pintype "passive"))
      (node (ref "SIDE16") (pin "23") (pinfunction "23_23") (pintype "passive"))
      (node (ref "SIDE16") (pin "25") (pinfunction "25_25") (pintype "passive"))
      (node (ref "SIDE16") (pin "27") (pinfunction "27_27") (pintype "passive"))
      (node (ref "SIDE16") (pin "29") (pinfunction "29_29") (pintype "passive"))
      (node (ref "SIDE16") (pin "3") (pinfunction "3_3") (pintype "passive"))
      (node (ref "SIDE16") (pin "31") (pinfunction "31_31") (pintype "passive"))
      (node (ref "SIDE16") (pin "33") (pinfunction "33_33") (pintype "passive"))
      (node (ref "SIDE16") (pin "5") (pinfunction "5_5") (pintype "passive"))
      (node (ref "SIDE16") (pin "7") (pinfunction "7_7") (pintype "passive"))
      (node (ref "SIDE16") (pin "9") (pinfunction "9_9") (pintype "passive"))
    )
    (net (code "268") (name "Net-(A8F-P$2)") (class "Default")
      (node (ref "A8") (pin "C2") (pinfunction "P$2_C2") (pintype "bidirectional"))
      (node (ref "SIDE15") (pin "1") (pinfunction "1_1") (pintype "passive"))
      (node (ref "SIDE15") (pin "11") (pinfunction "11_11") (pintype "passive"))
      (node (ref "SIDE15") (pin "13") (pinfunction "13_13") (pintype "passive"))
      (node (ref "SIDE15") (pin "15") (pinfunction "15_15") (pintype "passive"))
      (node (ref "SIDE15") (pin "17") (pinfunction "17_17") (pintype "passive"))
      (node (ref "SIDE15") (pin "19") (pinfunction "19_19") (pintype "passive"))
      (node (ref "SIDE15") (pin "21") (pinfunction "21_21") (pintype "passive"))
      (node (ref "SIDE15") (pin "23") (pinfunction "23_23") (pintype "passive"))
      (node (ref "SIDE15") (pin "25") (pinfunction "25_25") (pintype "passive"))
      (node (ref "SIDE15") (pin "27") (pinfunction "27_27") (pintype "passive"))
      (node (ref "SIDE15") (pin "29") (pinfunction "29_29") (pintype "passive"))
      (node (ref "SIDE15") (pin "3") (pinfunction "3_3") (pintype "passive"))
      (node (ref "SIDE15") (pin "31") (pinfunction "31_31") (pintype "passive"))
      (node (ref "SIDE15") (pin "33") (pinfunction "33_33") (pintype "passive"))
      (node (ref "SIDE15") (pin "5") (pinfunction "5_5") (pintype "passive"))
      (node (ref "SIDE15") (pin "7") (pinfunction "7_7") (pintype "passive"))
      (node (ref "SIDE15") (pin "9") (pinfunction "9_9") (pintype "passive"))
    )
    (net (code "269") (name "Net-(A8G-P$2)") (class "Default")
      (node (ref "A8") (pin "D1") (pinfunction "P$2_D1") (pintype "bidirectional"))
      (node (ref "SIDE16") (pin "8") (pinfunction "8_8") (pintype "passive"))
    )
    (net (code "270") (name "Net-(A8H-P$2)") (class "Default")
      (node (ref "A8") (pin "D2") (pinfunction "P$2_D2") (pintype "bidirectional"))
      (node (ref "SIDE15") (pin "6") (pinfunction "6_6") (pintype "passive"))
    )
    (net (code "271") (name "Net-(A8I-P$2)") (class "Default")
      (node (ref "A8") (pin "E1") (pinfunction "P$2_E1") (pintype "bidirectional"))
      (node (ref "SIDE16") (pin "12") (pinfunction "12_12") (pintype "passive"))
    )
    (net (code "272") (name "Net-(A8J-P$2)") (class "Default")
      (node (ref "A8") (pin "E2") (pinfunction "P$2_E2") (pintype "bidirectional"))
      (node (ref "SIDE15") (pin "8") (pinfunction "8_8") (pintype "passive"))
    )
    (net (code "273") (name "Net-(A8K-P$2)") (class "Default")
      (node (ref "A8") (pin "F1") (pinfunction "P$2_F1") (pintype "bidirectional"))
      (node (ref "SIDE16") (pin "14") (pinfunction "14_14") (pintype "passive"))
    )
    (net (code "274") (name "Net-(A8L-P$2)") (class "Default")
      (node (ref "A8") (pin "F2") (pinfunction "P$2_F2") (pintype "bidirectional"))
      (node (ref "SIDE15") (pin "10") (pinfunction "10_10") (pintype "passive"))
    )
    (net (code "275") (name "Net-(A8M-P$2)") (class "Default")
      (node (ref "A8") (pin "H1") (pinfunction "P$2_H1") (pintype "bidirectional"))
      (node (ref "SIDE16") (pin "16") (pinfunction "16_16") (pintype "passive"))
    )
    (net (code "276") (name "Net-(A8N-P$2)") (class "Default")
      (node (ref "A8") (pin "H2") (pinfunction "P$2_H2") (pintype "bidirectional"))
      (node (ref "SIDE15") (pin "12") (pinfunction "12_12") (pintype "passive"))
    )
    (net (code "277") (name "Net-(A8O-P$2)") (class "Default")
      (node (ref "A8") (pin "J1") (pinfunction "P$2_J1") (pintype "bidirectional"))
      (node (ref "SIDE16") (pin "20") (pinfunction "20_20") (pintype "passive"))
    )
    (net (code "278") (name "Net-(A8P-P$2)") (class "Default")
      (node (ref "A8") (pin "J2") (pinfunction "P$2_J2") (pintype "bidirectional"))
      (node (ref "SIDE15") (pin "14") (pinfunction "14_14") (pintype "passive"))
    )
    (net (code "279") (name "Net-(A8Q-P$2)") (class "Default")
      (node (ref "A8") (pin "K1") (pinfunction "P$2_K1") (pintype "bidirectional"))
      (node (ref "SIDE16") (pin "18") (pinfunction "18_18") (pintype "passive"))
    )
    (net (code "280") (name "Net-(A8R-P$2)") (class "Default")
      (node (ref "A8") (pin "K2") (pinfunction "P$2_K2") (pintype "bidirectional"))
      (node (ref "SIDE15") (pin "16") (pinfunction "16_16") (pintype "passive"))
    )
    (net (code "281") (name "Net-(A8S-P$2)") (class "Default")
      (node (ref "A8") (pin "L1") (pinfunction "P$2_L1") (pintype "bidirectional"))
      (node (ref "SIDE16") (pin "24") (pinfunction "24_24") (pintype "passive"))
    )
    (net (code "282") (name "Net-(A8T-P$2)") (class "Default")
      (node (ref "A8") (pin "L2") (pinfunction "P$2_L2") (pintype "bidirectional"))
      (node (ref "SIDE15") (pin "18") (pinfunction "18_18") (pintype "passive"))
    )
    (net (code "283") (name "Net-(A8U-P$2)") (class "Default")
      (node (ref "A8") (pin "M1") (pinfunction "P$2_M1") (pintype "bidirectional"))
      (node (ref "SIDE16") (pin "28") (pinfunction "28_28") (pintype "passive"))
    )
    (net (code "284") (name "Net-(A8V-P$2)") (class "Default")
      (node (ref "A8") (pin "M2") (pinfunction "P$2_M2") (pintype "bidirectional"))
      (node (ref "SIDE15") (pin "20") (pinfunction "20_20") (pintype "passive"))
    )
    (net (code "285") (name "Net-(A8W-P$2)") (class "Default")
      (node (ref "A8") (pin "N1") (pinfunction "P$2_N1") (pintype "bidirectional"))
      (node (ref "SIDE16") (pin "22") (pinfunction "22_22") (pintype "passive"))
    )
    (net (code "286") (name "Net-(A8X-P$2)") (class "Default")
      (node (ref "A8") (pin "N2") (pinfunction "P$2_N2") (pintype "bidirectional"))
      (node (ref "SIDE15") (pin "22") (pinfunction "22_22") (pintype "passive"))
    )
    (net (code "287") (name "Net-(A8Y-P$2)") (class "Default")
      (node (ref "A8") (pin "P1") (pinfunction "P$2_P1") (pintype "bidirectional"))
      (node (ref "SIDE16") (pin "30") (pinfunction "30_30") (pintype "passive"))
    )
    (net (code "288") (name "Net-(A8Z-P$2)") (class "Default")
      (node (ref "A8") (pin "P2") (pinfunction "P$2_P2") (pintype "bidirectional"))
      (node (ref "SIDE15") (pin "24") (pinfunction "24_24") (pintype "passive"))
    )
  )
)
